# untitled.net
KiCad netlist of a schematic drawn in EAGLE
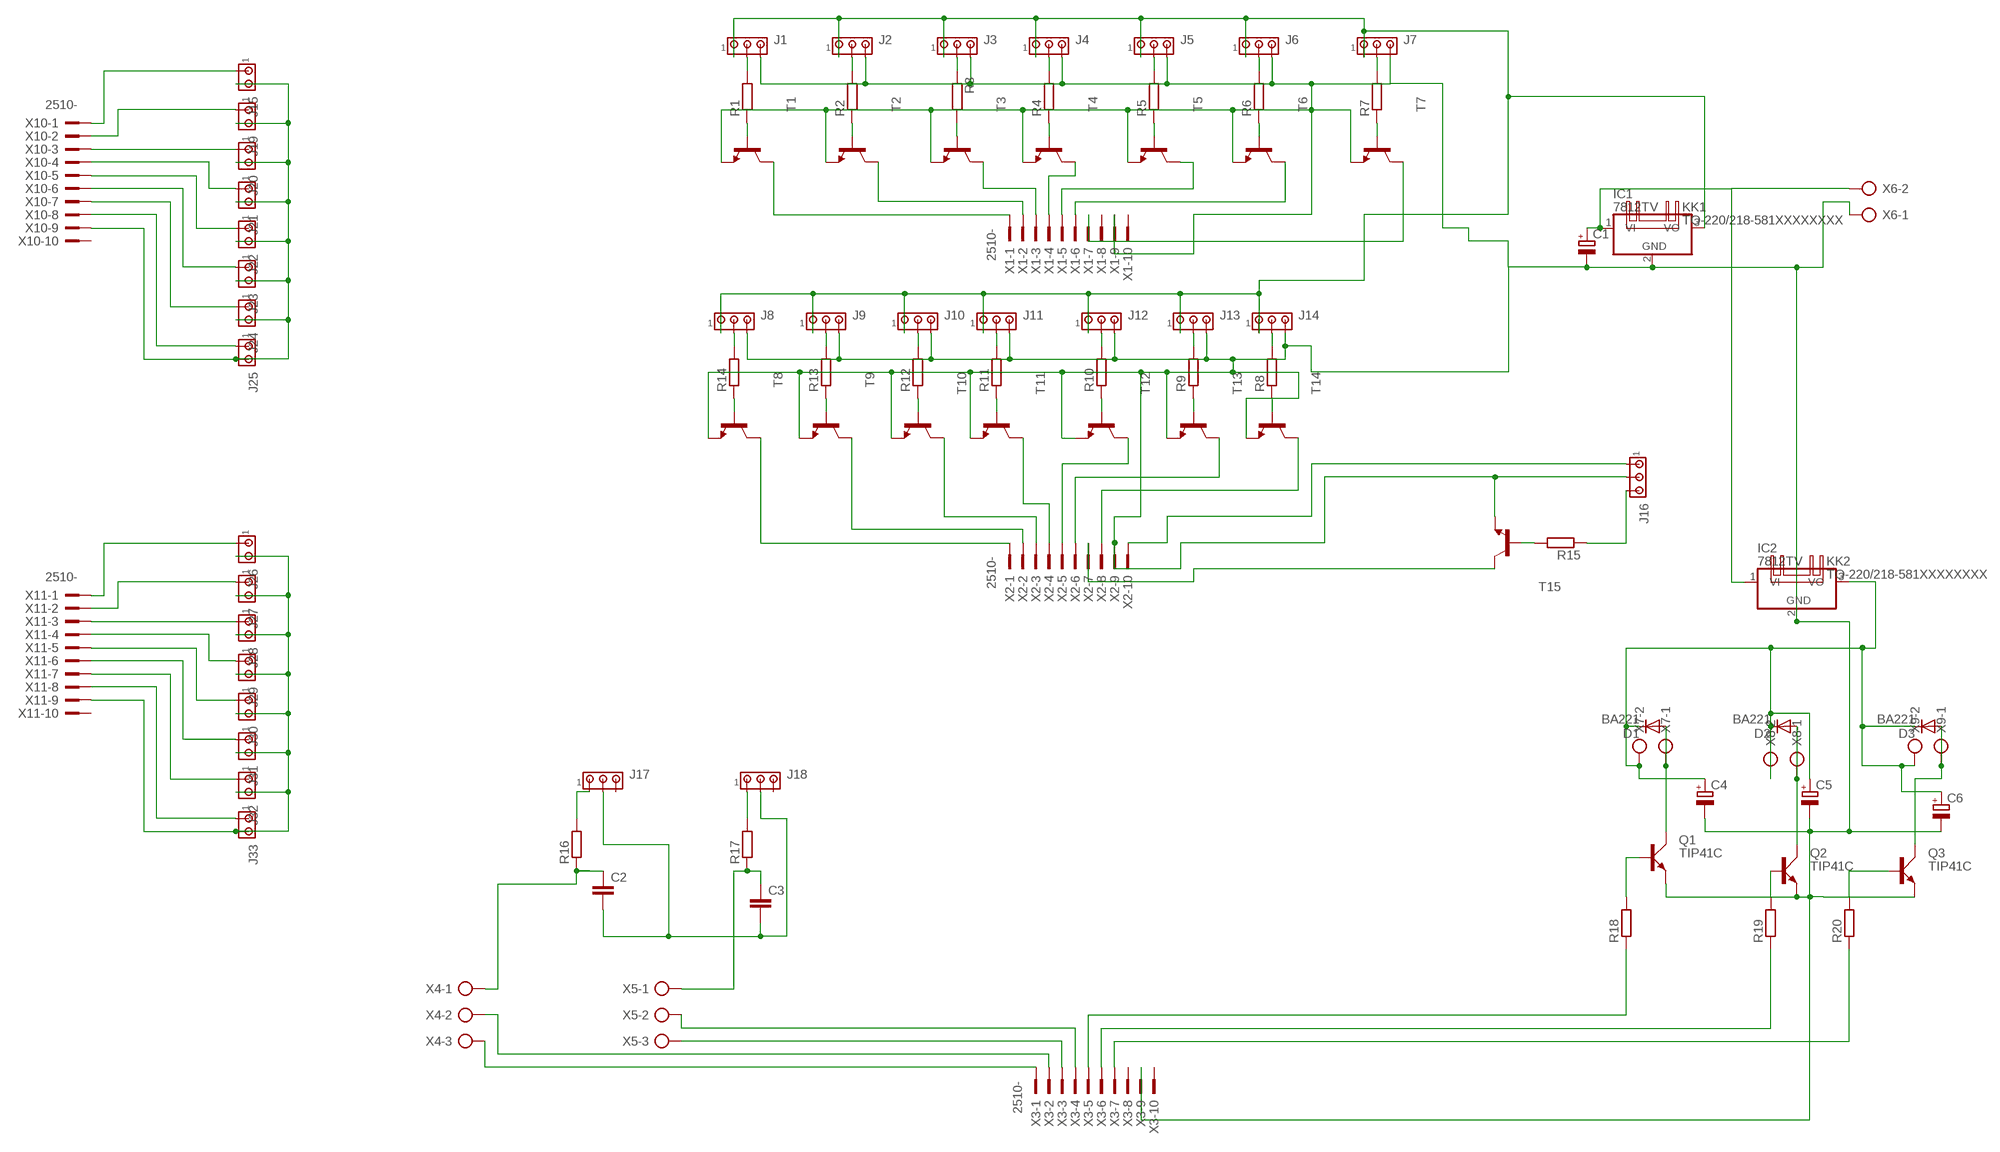
[diagram p0: schematic, sheet 1]
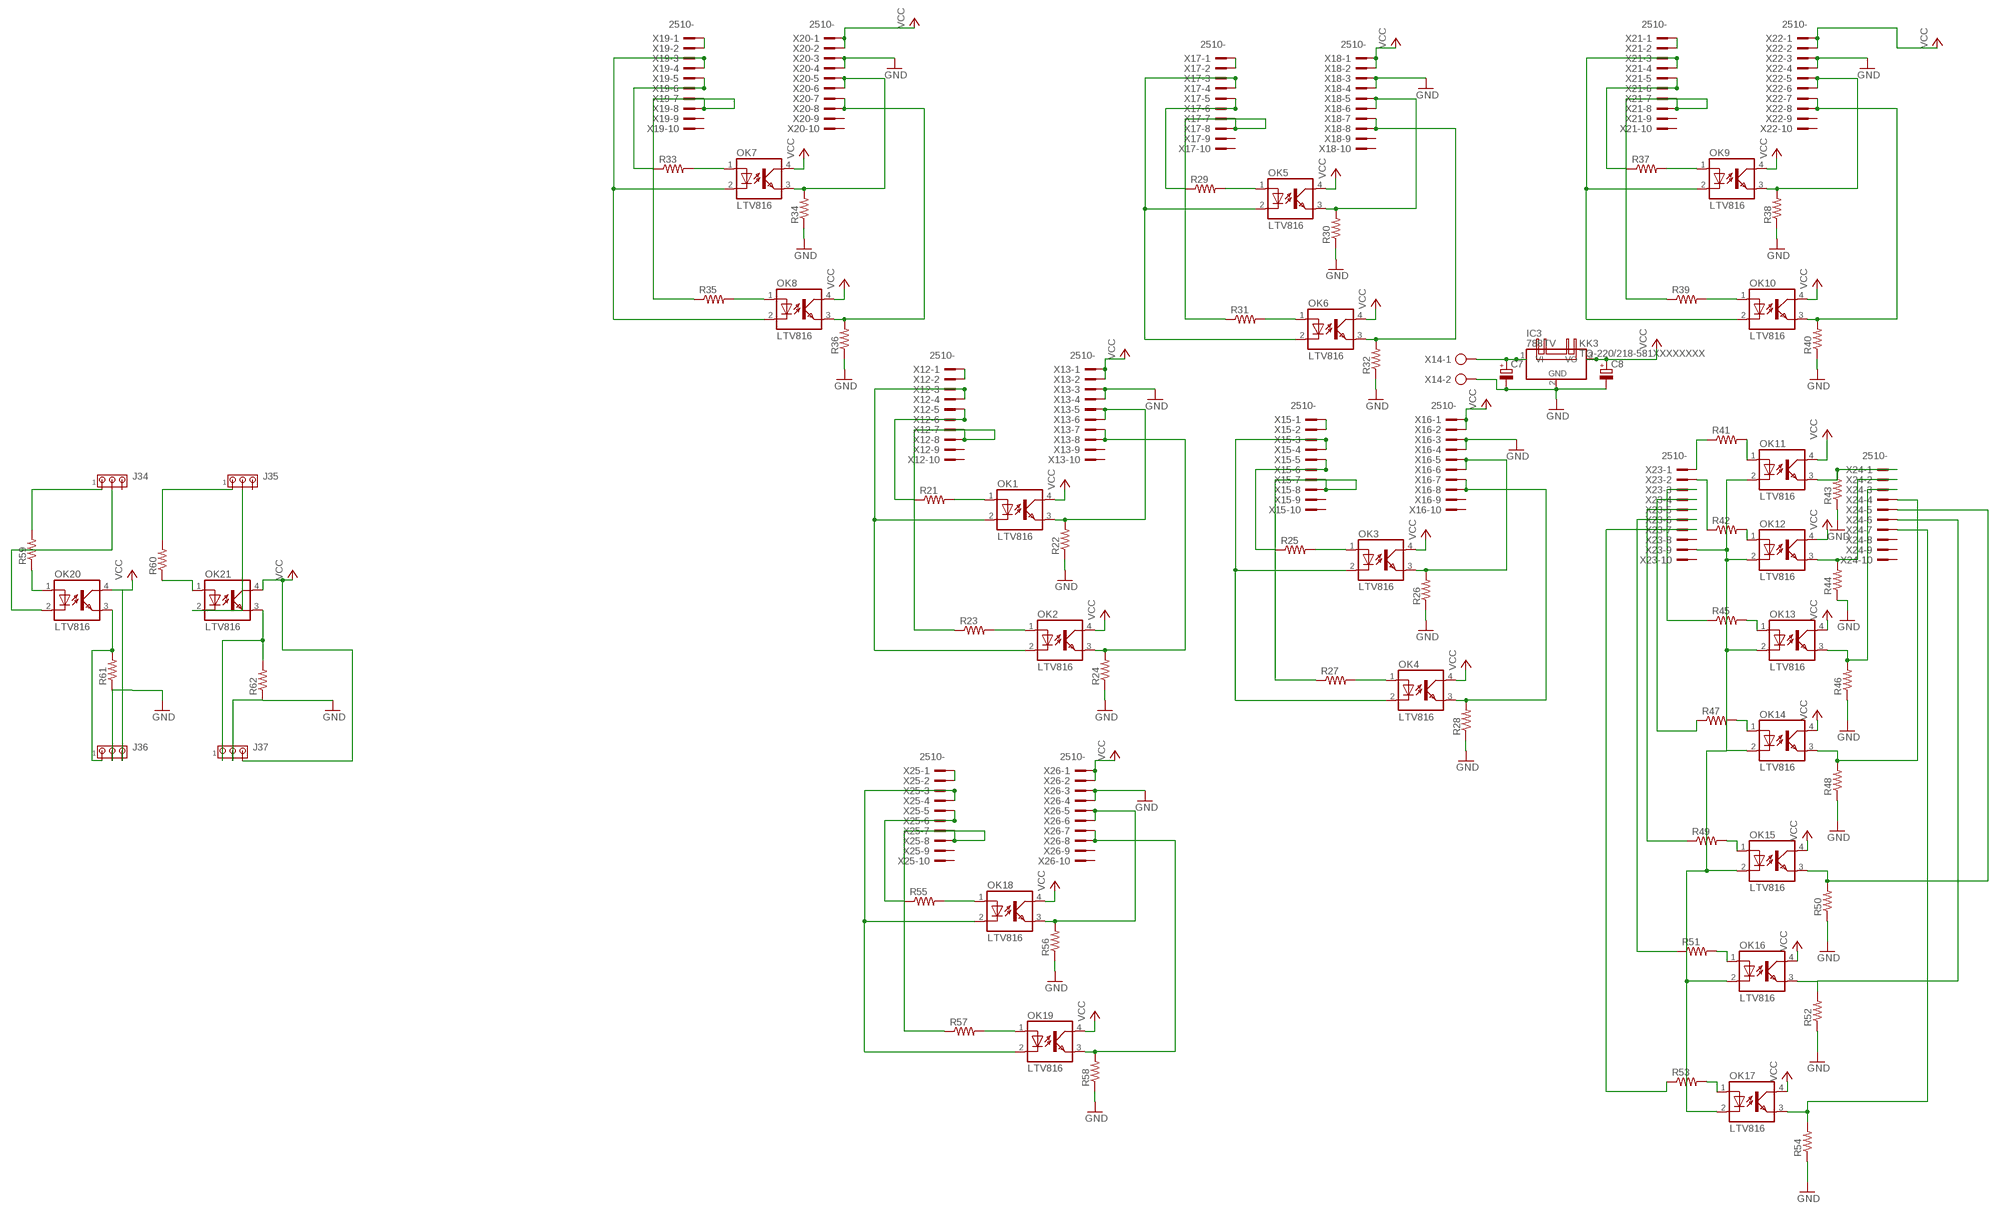
[diagram p1: schematic, sheet 2]

(export (version "E")
  (design (tool "Eeschema 10.0.6"))
  (components
    (comp (ref "C1")
      (value "CPOL-EUE5-10.5")
      (footprint "eagle-import:E5-10,5")
      (libsource (lib "eagle-import") (part "CPOL-EUE5-10.5"))
    )
    (comp (ref "C2")
      (value "C-EU375-192X418")
      (footprint "eagle-import:C375-192X418")
      (libsource (lib "eagle-import") (part "C-EU375-192X418"))
    )
    (comp (ref "C3")
      (value "C-EU375-192X418")
      (footprint "eagle-import:C375-192X418")
      (libsource (lib "eagle-import") (part "C-EU375-192X418"))
    )
    (comp (ref "C4")
      (value "CPOL-EUE5-13")
      (footprint "eagle-import:E5-13")
      (libsource (lib "eagle-import") (part "resistor_CPOL-EUE5-13"))
    )
    (comp (ref "C5")
      (value "CPOL-EUE5-13")
      (footprint "eagle-import:E5-13")
      (libsource (lib "eagle-import") (part "resistor_CPOL-EUE5-13"))
    )
    (comp (ref "C6")
      (value "CPOL-EUE5-13")
      (footprint "eagle-import:E5-13")
      (libsource (lib "eagle-import") (part "resistor_CPOL-EUE5-13"))
    )
    (comp (ref "D1")
      (value "BA221")
      (footprint "eagle-import:DO35-10")
      (libsource (lib "eagle-import") (part "BA221"))
    )
    (comp (ref "D2")
      (value "BA221")
      (footprint "eagle-import:DO35-10")
      (libsource (lib "eagle-import") (part "BA221"))
    )
    (comp (ref "D3")
      (value "BA221")
      (footprint "eagle-import:DO35-10")
      (libsource (lib "eagle-import") (part "BA221"))
    )
    (comp (ref "IC1")
      (value "7812TV")
      (footprint "eagle-import:TO220V")
      (libsource (lib "eagle-import") (part "78TV12"))
    )
    (comp (ref "IC2")
      (value "7812TV")
      (footprint "eagle-import:TO220V")
      (libsource (lib "eagle-import") (part "78TV12"))
    )
    (comp (ref "J1")
      (value "MTA03-100")
      (footprint "eagle-import:10X03MTA")
      (libsource (lib "eagle-import") (part "MTA03-100"))
    )
    (comp (ref "J2")
      (value "MTA03-100")
      (footprint "eagle-import:10X03MTA")
      (libsource (lib "eagle-import") (part "MTA03-100"))
    )
    (comp (ref "J3")
      (value "MTA03-100")
      (footprint "eagle-import:10X03MTA")
      (libsource (lib "eagle-import") (part "MTA03-100"))
    )
    (comp (ref "J4")
      (value "MTA03-100")
      (footprint "eagle-import:10X03MTA")
      (libsource (lib "eagle-import") (part "MTA03-100"))
    )
    (comp (ref "J5")
      (value "MTA03-100")
      (footprint "eagle-import:10X03MTA")
      (libsource (lib "eagle-import") (part "MTA03-100"))
    )
    (comp (ref "J6")
      (value "MTA03-100")
      (footprint "eagle-import:10X03MTA")
      (libsource (lib "eagle-import") (part "MTA03-100"))
    )
    (comp (ref "J7")
      (value "MTA03-100")
      (footprint "eagle-import:10X03MTA")
      (libsource (lib "eagle-import") (part "MTA03-100"))
    )
    (comp (ref "J8")
      (value "MTA03-100")
      (footprint "eagle-import:10X03MTA")
      (libsource (lib "eagle-import") (part "MTA03-100"))
    )
    (comp (ref "J9")
      (value "MTA03-100")
      (footprint "eagle-import:10X03MTA")
      (libsource (lib "eagle-import") (part "MTA03-100"))
    )
    (comp (ref "J10")
      (value "MTA03-100")
      (footprint "eagle-import:10X03MTA")
      (libsource (lib "eagle-import") (part "MTA03-100"))
    )
    (comp (ref "J11")
      (value "MTA03-100")
      (footprint "eagle-import:10X03MTA")
      (libsource (lib "eagle-import") (part "MTA03-100"))
    )
    (comp (ref "J12")
      (value "MTA03-100")
      (footprint "eagle-import:10X03MTA")
      (libsource (lib "eagle-import") (part "MTA03-100"))
    )
    (comp (ref "J13")
      (value "MTA03-100")
      (footprint "eagle-import:10X03MTA")
      (libsource (lib "eagle-import") (part "MTA03-100"))
    )
    (comp (ref "J14")
      (value "MTA03-100")
      (footprint "eagle-import:10X03MTA")
      (libsource (lib "eagle-import") (part "MTA03-100"))
    )
    (comp (ref "J15")
      (value "MTA02-100")
      (footprint "eagle-import:10X02MTA")
      (libsource (lib "eagle-import") (part "MTA02-100"))
    )
    (comp (ref "J16")
      (value "MTA03-100")
      (footprint "eagle-import:10X03MTA")
      (libsource (lib "eagle-import") (part "MTA03-100"))
    )
    (comp (ref "J17")
      (value "MTA03-100")
      (footprint "eagle-import:10X03MTA")
      (libsource (lib "eagle-import") (part "MTA03-100"))
    )
    (comp (ref "J18")
      (value "MTA03-100")
      (footprint "eagle-import:10X03MTA")
      (libsource (lib "eagle-import") (part "MTA03-100"))
    )
    (comp (ref "J19")
      (value "MTA02-100")
      (footprint "eagle-import:10X02MTA")
      (libsource (lib "eagle-import") (part "MTA02-100"))
    )
    (comp (ref "J20")
      (value "MTA02-100")
      (footprint "eagle-import:10X02MTA")
      (libsource (lib "eagle-import") (part "MTA02-100"))
    )
    (comp (ref "J21")
      (value "MTA02-100")
      (footprint "eagle-import:10X02MTA")
      (libsource (lib "eagle-import") (part "MTA02-100"))
    )
    (comp (ref "J22")
      (value "MTA02-100")
      (footprint "eagle-import:10X02MTA")
      (libsource (lib "eagle-import") (part "MTA02-100"))
    )
    (comp (ref "J23")
      (value "MTA02-100")
      (footprint "eagle-import:10X02MTA")
      (libsource (lib "eagle-import") (part "MTA02-100"))
    )
    (comp (ref "J24")
      (value "MTA02-100")
      (footprint "eagle-import:10X02MTA")
      (libsource (lib "eagle-import") (part "MTA02-100"))
    )
    (comp (ref "J25")
      (value "MTA02-100")
      (footprint "eagle-import:10X02MTA")
      (libsource (lib "eagle-import") (part "MTA02-100"))
    )
    (comp (ref "J26")
      (value "MTA02-100")
      (footprint "eagle-import:10X02MTA")
      (libsource (lib "eagle-import") (part "MTA02-100"))
    )
    (comp (ref "J27")
      (value "MTA02-100")
      (footprint "eagle-import:10X02MTA")
      (libsource (lib "eagle-import") (part "MTA02-100"))
    )
    (comp (ref "J28")
      (value "MTA02-100")
      (footprint "eagle-import:10X02MTA")
      (libsource (lib "eagle-import") (part "MTA02-100"))
    )
    (comp (ref "J29")
      (value "MTA02-100")
      (footprint "eagle-import:10X02MTA")
      (libsource (lib "eagle-import") (part "MTA02-100"))
    )
    (comp (ref "J30")
      (value "MTA02-100")
      (footprint "eagle-import:10X02MTA")
      (libsource (lib "eagle-import") (part "MTA02-100"))
    )
    (comp (ref "J31")
      (value "MTA02-100")
      (footprint "eagle-import:10X02MTA")
      (libsource (lib "eagle-import") (part "MTA02-100"))
    )
    (comp (ref "J32")
      (value "MTA02-100")
      (footprint "eagle-import:10X02MTA")
      (libsource (lib "eagle-import") (part "MTA02-100"))
    )
    (comp (ref "J33")
      (value "MTA02-100")
      (footprint "eagle-import:10X02MTA")
      (libsource (lib "eagle-import") (part "MTA02-100"))
    )
    (comp (ref "KK1")
      (value "TO-220/218-581XXXXXXXX")
      (footprint "eagle-import:581XXXXXXXX")
      (libsource (lib "eagle-import") (part "TO-220/218-581XXXXXXXX"))
    )
    (comp (ref "KK2")
      (value "TO-220/218-581XXXXXXXX")
      (footprint "eagle-import:581XXXXXXXX")
      (libsource (lib "eagle-import") (part "TO-220/218-581XXXXXXXX"))
    )
    (comp (ref "Q1")
      (value "TIP41C")
      (footprint "eagle-import:TO220AV")
      (libsource (lib "eagle-import") (part "TIP41C"))
    )
    (comp (ref "Q2")
      (value "TIP41C")
      (footprint "eagle-import:TO220AV")
      (libsource (lib "eagle-import") (part "TIP41C"))
    )
    (comp (ref "Q3")
      (value "TIP41C")
      (footprint "eagle-import:TO220AV")
      (libsource (lib "eagle-import") (part "TIP41C"))
    )
    (comp (ref "R1")
      (value "R-EU_0207/10")
      (footprint "eagle-import:0207_10")
      (libsource (lib "eagle-import") (part "R-EU_0207/10"))
    )
    (comp (ref "R2")
      (value "R-EU_0207/10")
      (footprint "eagle-import:0207_10")
      (libsource (lib "eagle-import") (part "R-EU_0207/10"))
    )
    (comp (ref "R3")
      (value "R-EU_0207/10")
      (footprint "eagle-import:0207_10")
      (libsource (lib "eagle-import") (part "R-EU_0207/10"))
    )
    (comp (ref "R4")
      (value "R-EU_0207/10")
      (footprint "eagle-import:0207_10")
      (libsource (lib "eagle-import") (part "R-EU_0207/10"))
    )
    (comp (ref "R5")
      (value "R-EU_0207/10")
      (footprint "eagle-import:0207_10")
      (libsource (lib "eagle-import") (part "R-EU_0207/10"))
    )
    (comp (ref "R6")
      (value "R-EU_0207/10")
      (footprint "eagle-import:0207_10")
      (libsource (lib "eagle-import") (part "R-EU_0207/10"))
    )
    (comp (ref "R7")
      (value "R-EU_0207/10")
      (footprint "eagle-import:0207_10")
      (libsource (lib "eagle-import") (part "R-EU_0207/10"))
    )
    (comp (ref "R8")
      (value "R-EU_0207/10")
      (footprint "eagle-import:0207_10")
      (libsource (lib "eagle-import") (part "R-EU_0207/10"))
    )
    (comp (ref "R9")
      (value "R-EU_0207/10")
      (footprint "eagle-import:0207_10")
      (libsource (lib "eagle-import") (part "R-EU_0207/10"))
    )
    (comp (ref "R10")
      (value "R-EU_0207/10")
      (footprint "eagle-import:0207_10")
      (libsource (lib "eagle-import") (part "R-EU_0207/10"))
    )
    (comp (ref "R11")
      (value "R-EU_0207/10")
      (footprint "eagle-import:0207_10")
      (libsource (lib "eagle-import") (part "R-EU_0207/10"))
    )
    (comp (ref "R12")
      (value "R-EU_0207/10")
      (footprint "eagle-import:0207_10")
      (libsource (lib "eagle-import") (part "R-EU_0207/10"))
    )
    (comp (ref "R13")
      (value "R-EU_0207/10")
      (footprint "eagle-import:0207_10")
      (libsource (lib "eagle-import") (part "R-EU_0207/10"))
    )
    (comp (ref "R14")
      (value "R-EU_0207/10")
      (footprint "eagle-import:0207_10")
      (libsource (lib "eagle-import") (part "R-EU_0207/10"))
    )
    (comp (ref "R15")
      (value "R-EU_0207/10")
      (footprint "eagle-import:0207_10")
      (libsource (lib "eagle-import") (part "R-EU_0207/10"))
    )
    (comp (ref "R16")
      (value "R-EU_0207/10")
      (footprint "eagle-import:0207_10")
      (libsource (lib "eagle-import") (part "R-EU_0207/10"))
    )
    (comp (ref "R17")
      (value "R-EU_0207/10")
      (footprint "eagle-import:0207_10")
      (libsource (lib "eagle-import") (part "R-EU_0207/10"))
    )
    (comp (ref "R18")
      (value "R-EU_0207/10")
      (footprint "eagle-import:0207_10")
      (libsource (lib "eagle-import") (part "R-EU_0207/10"))
    )
    (comp (ref "R19")
      (value "R-EU_0207/10")
      (footprint "eagle-import:0207_10")
      (libsource (lib "eagle-import") (part "R-EU_0207/10"))
    )
    (comp (ref "R20")
      (value "R-EU_0207/10")
      (footprint "eagle-import:0207_10")
      (libsource (lib "eagle-import") (part "R-EU_0207/10"))
    )
    (comp (ref "T1")
      (value "2N5401-NPN-TO92-CBE")
      (footprint "eagle-import:TO92-CBE")
      (libsource (lib "eagle-import") (part "-NPN-TO92-CBE2N5401"))
    )
    (comp (ref "T2")
      (value "2N5401-NPN-TO92-CBE")
      (footprint "eagle-import:TO92-CBE")
      (libsource (lib "eagle-import") (part "-NPN-TO92-CBE2N5401"))
    )
    (comp (ref "T3")
      (value "2N5401-NPN-TO92-CBE")
      (footprint "eagle-import:TO92-CBE")
      (libsource (lib "eagle-import") (part "-NPN-TO92-CBE2N5401"))
    )
    (comp (ref "T4")
      (value "2N5401-NPN-TO92-CBE")
      (footprint "eagle-import:TO92-CBE")
      (libsource (lib "eagle-import") (part "-NPN-TO92-CBE2N5401"))
    )
    (comp (ref "T5")
      (value "2N5401-NPN-TO92-CBE")
      (footprint "eagle-import:TO92-CBE")
      (libsource (lib "eagle-import") (part "-NPN-TO92-CBE2N5401"))
    )
    (comp (ref "T6")
      (value "2N5401-NPN-TO92-CBE")
      (footprint "eagle-import:TO92-CBE")
      (libsource (lib "eagle-import") (part "-NPN-TO92-CBE2N5401"))
    )
    (comp (ref "T7")
      (value "2N5401-NPN-TO92-CBE")
      (footprint "eagle-import:TO92-CBE")
      (libsource (lib "eagle-import") (part "-NPN-TO92-CBE2N5401"))
    )
    (comp (ref "T8")
      (value "2N5401-NPN-TO92-CBE")
      (footprint "eagle-import:TO92-CBE")
      (libsource (lib "eagle-import") (part "-NPN-TO92-CBE2N5401"))
    )
    (comp (ref "T9")
      (value "2N5401-NPN-TO92-CBE")
      (footprint "eagle-import:TO92-CBE")
      (libsource (lib "eagle-import") (part "-NPN-TO92-CBE2N5401"))
    )
    (comp (ref "T10")
      (value "2N5401-NPN-TO92-CBE")
      (footprint "eagle-import:TO92-CBE")
      (libsource (lib "eagle-import") (part "-NPN-TO92-CBE2N5401"))
    )
    (comp (ref "T11")
      (value "2N5401-NPN-TO92-CBE")
      (footprint "eagle-import:TO92-CBE")
      (libsource (lib "eagle-import") (part "-NPN-TO92-CBE2N5401"))
    )
    (comp (ref "T12")
      (value "2N5401-NPN-TO92-CBE")
      (footprint "eagle-import:TO92-CBE")
      (libsource (lib "eagle-import") (part "-NPN-TO92-CBE2N5401"))
    )
    (comp (ref "T13")
      (value "2N5401-NPN-TO92-CBE")
      (footprint "eagle-import:TO92-CBE")
      (libsource (lib "eagle-import") (part "-NPN-TO92-CBE2N5401"))
    )
    (comp (ref "T14")
      (value "2N5401-NPN-TO92-CBE")
      (footprint "eagle-import:TO92-CBE")
      (libsource (lib "eagle-import") (part "-NPN-TO92-CBE2N5401"))
    )
    (comp (ref "T15")
      (value "2N5401-NPN-TO92-CBE")
      (footprint "eagle-import:TO92-CBE")
      (libsource (lib "eagle-import") (part "-NPN-TO92-CBE2N5401"))
    )
    (comp (ref "X1")
      (value "2510-")
      (footprint "eagle-import:PAK100_2500-10")
      (fields (field (name "MF") "3M") (field (name "MPN") "2510-6002UB"))
      (libsource (lib "eagle-import") (part "2510-"))
    )
    (comp (ref "X2")
      (value "2510-")
      (footprint "eagle-import:PAK100_2500-10")
      (fields (field (name "MF") "3M") (field (name "MPN") "2510-6002UB"))
      (libsource (lib "eagle-import") (part "2510-"))
    )
    (comp (ref "X3")
      (value "2510-")
      (footprint "eagle-import:PAK100_2500-10")
      (fields (field (name "MF") "3M") (field (name "MPN") "2510-6002UB"))
      (libsource (lib "eagle-import") (part "2510-"))
    )
    (comp (ref "X4")
      (value "AK300/3")
      (footprint "eagle-import:AK300_3")
      (libsource (lib "eagle-import") (part "AK300/3"))
    )
    (comp (ref "X5")
      (value "AK300/3")
      (footprint "eagle-import:AK300_3")
      (libsource (lib "eagle-import") (part "AK300/3"))
    )
    (comp (ref "X6")
      (value "AK300/2")
      (footprint "eagle-import:AK300_2")
      (libsource (lib "eagle-import") (part "AK300/2"))
    )
    (comp (ref "X7")
      (value "AK300/2")
      (footprint "eagle-import:AK300_2")
      (libsource (lib "eagle-import") (part "AK300/2"))
    )
    (comp (ref "X8")
      (value "AK300/2")
      (footprint "eagle-import:AK300_2")
      (libsource (lib "eagle-import") (part "AK300/2"))
    )
    (comp (ref "X9")
      (value "AK300/2")
      (footprint "eagle-import:AK300_2")
      (libsource (lib "eagle-import") (part "AK300/2"))
    )
    (comp (ref "X10")
      (value "2510-")
      (footprint "eagle-import:PAK100_2500-10")
      (fields (field (name "MF") "3M") (field (name "MPN") "2510-6002UB"))
      (libsource (lib "eagle-import") (part "2510-"))
    )
    (comp (ref "X11")
      (value "2510-")
      (footprint "eagle-import:PAK100_2500-10")
      (fields (field (name "MF") "3M") (field (name "MPN") "2510-6002UB"))
      (libsource (lib "eagle-import") (part "2510-"))
    )
    (comp (ref "C7")
      (value "CPOL-EUE5-13")
      (footprint "eagle-import:E5-13")
      (libsource (lib "eagle-import") (part "CPOL-EUE5-13"))
    )
    (comp (ref "C8")
      (value "CPOL-EUE5-10.5")
      (footprint "eagle-import:E5-10,5")
      (libsource (lib "eagle-import") (part "CPOL-EUE5-10.5"))
    )
    (comp (ref "IC3")
      (value "788TV")
      (footprint "eagle-import:TO220V")
      (libsource (lib "eagle-import") (part "78TV8"))
    )
    (comp (ref "J34")
      (value "MTA03-100")
      (footprint "eagle-import:10X03MTA")
      (libsource (lib "eagle-import") (part "MTA03-100"))
    )
    (comp (ref "J35")
      (value "MTA03-100")
      (footprint "eagle-import:10X03MTA")
      (libsource (lib "eagle-import") (part "MTA03-100"))
    )
    (comp (ref "J36")
      (value "MTA03-100")
      (footprint "eagle-import:10X03MTA")
      (libsource (lib "eagle-import") (part "MTA03-100"))
    )
    (comp (ref "J37")
      (value "MTA03-100")
      (footprint "eagle-import:10X03MTA")
      (libsource (lib "eagle-import") (part "MTA03-100"))
    )
    (comp (ref "KK3")
      (value "TO-220/218-581XXXXXXXX")
      (footprint "eagle-import:581XXXXXXXX")
      (libsource (lib "eagle-import") (part "TO-220/218-581XXXXXXXX"))
    )
    (comp (ref "OK1")
      (value "LTV816")
      (footprint "eagle-import:DIL04")
      (libsource (lib "eagle-import") (part "LTV816"))
    )
    (comp (ref "OK2")
      (value "LTV816")
      (footprint "eagle-import:DIL04")
      (libsource (lib "eagle-import") (part "LTV816"))
    )
    (comp (ref "OK3")
      (value "LTV816")
      (footprint "eagle-import:DIL04")
      (libsource (lib "eagle-import") (part "LTV816"))
    )
    (comp (ref "OK4")
      (value "LTV816")
      (footprint "eagle-import:DIL04")
      (libsource (lib "eagle-import") (part "LTV816"))
    )
    (comp (ref "OK5")
      (value "LTV816")
      (footprint "eagle-import:DIL04")
      (libsource (lib "eagle-import") (part "LTV816"))
    )
    (comp (ref "OK6")
      (value "LTV816")
      (footprint "eagle-import:DIL04")
      (libsource (lib "eagle-import") (part "LTV816"))
    )
    (comp (ref "OK7")
      (value "LTV816")
      (footprint "eagle-import:DIL04")
      (libsource (lib "eagle-import") (part "LTV816"))
    )
    (comp (ref "OK8")
      (value "LTV816")
      (footprint "eagle-import:DIL04")
      (libsource (lib "eagle-import") (part "LTV816"))
    )
    (comp (ref "OK9")
      (value "LTV816")
      (footprint "eagle-import:DIL04")
      (libsource (lib "eagle-import") (part "LTV816"))
    )
    (comp (ref "OK10")
      (value "LTV816")
      (footprint "eagle-import:DIL04")
      (libsource (lib "eagle-import") (part "LTV816"))
    )
    (comp (ref "OK11")
      (value "LTV816")
      (footprint "eagle-import:DIL04")
      (fields (field (name "OC_FARNELL") "unknown") (field (name "OC_NEWARK") "unknown"))
      (libsource (lib "eagle-import") (part "LTV816"))
    )
    (comp (ref "OK12")
      (value "LTV816")
      (footprint "eagle-import:DIL04")
      (fields (field (name "OC_FARNELL") "unknown") (field (name "OC_NEWARK") "unknown"))
      (libsource (lib "eagle-import") (part "LTV816"))
    )
    (comp (ref "OK13")
      (value "LTV816")
      (footprint "eagle-import:DIL04")
      (fields (field (name "OC_FARNELL") "unknown") (field (name "OC_NEWARK") "unknown"))
      (libsource (lib "eagle-import") (part "LTV816"))
    )
    (comp (ref "OK14")
      (value "LTV816")
      (footprint "eagle-import:DIL04")
      (fields (field (name "OC_FARNELL") "unknown") (field (name "OC_NEWARK") "unknown"))
      (libsource (lib "eagle-import") (part "LTV816"))
    )
    (comp (ref "OK15")
      (value "LTV816")
      (footprint "eagle-import:DIL04")
      (fields (field (name "OC_FARNELL") "unknown") (field (name "OC_NEWARK") "unknown"))
      (libsource (lib "eagle-import") (part "LTV816"))
    )
    (comp (ref "OK16")
      (value "LTV816")
      (footprint "eagle-import:DIL04")
      (fields (field (name "OC_FARNELL") "unknown") (field (name "OC_NEWARK") "unknown"))
      (libsource (lib "eagle-import") (part "LTV816"))
    )
    (comp (ref "OK17")
      (value "LTV816")
      (footprint "eagle-import:DIL04")
      (fields (field (name "OC_FARNELL") "unknown") (field (name "OC_NEWARK") "unknown"))
      (libsource (lib "eagle-import") (part "LTV816"))
    )
    (comp (ref "OK18")
      (value "LTV816")
      (footprint "eagle-import:DIL04")
      (libsource (lib "eagle-import") (part "LTV816"))
    )
    (comp (ref "OK19")
      (value "LTV816")
      (footprint "eagle-import:DIL04")
      (libsource (lib "eagle-import") (part "LTV816"))
    )
    (comp (ref "OK20")
      (value "LTV816")
      (footprint "eagle-import:DIL04")
      (fields (field (name "OC_FARNELL") "unknown") (field (name "OC_NEWARK") "unknown"))
      (libsource (lib "eagle-import") (part "LTV816"))
    )
    (comp (ref "OK21")
      (value "LTV816")
      (footprint "eagle-import:DIL04")
      (fields (field (name "OC_FARNELL") "unknown") (field (name "OC_NEWARK") "unknown"))
      (libsource (lib "eagle-import") (part "LTV816"))
    )
    (comp (ref "R21")
      (value "R-US_0207/10")
      (footprint "eagle-import:0207_10")
      (libsource (lib "eagle-import") (part "R-US_0207/10"))
    )
    (comp (ref "R22")
      (value "R-US_0207/10")
      (footprint "eagle-import:0207_10")
      (libsource (lib "eagle-import") (part "R-US_0207/10"))
    )
    (comp (ref "R23")
      (value "R-US_0207/10")
      (footprint "eagle-import:0207_10")
      (libsource (lib "eagle-import") (part "R-US_0207/10"))
    )
    (comp (ref "R24")
      (value "R-US_0207/10")
      (footprint "eagle-import:0207_10")
      (libsource (lib "eagle-import") (part "R-US_0207/10"))
    )
    (comp (ref "R25")
      (value "R-US_0207/10")
      (footprint "eagle-import:0207_10")
      (libsource (lib "eagle-import") (part "R-US_0207/10"))
    )
    (comp (ref "R26")
      (value "R-US_0207/10")
      (footprint "eagle-import:0207_10")
      (libsource (lib "eagle-import") (part "R-US_0207/10"))
    )
    (comp (ref "R27")
      (value "R-US_0207/10")
      (footprint "eagle-import:0207_10")
      (libsource (lib "eagle-import") (part "R-US_0207/10"))
    )
    (comp (ref "R28")
      (value "R-US_0207/10")
      (footprint "eagle-import:0207_10")
      (libsource (lib "eagle-import") (part "R-US_0207/10"))
    )
    (comp (ref "R29")
      (value "R-US_0207/10")
      (footprint "eagle-import:0207_10")
      (libsource (lib "eagle-import") (part "R-US_0207/10"))
    )
    (comp (ref "R30")
      (value "R-US_0207/10")
      (footprint "eagle-import:0207_10")
      (libsource (lib "eagle-import") (part "R-US_0207/10"))
    )
    (comp (ref "R31")
      (value "R-US_0207/10")
      (footprint "eagle-import:0207_10")
      (libsource (lib "eagle-import") (part "R-US_0207/10"))
    )
    (comp (ref "R32")
      (value "R-US_0207/10")
      (footprint "eagle-import:0207_10")
      (libsource (lib "eagle-import") (part "R-US_0207/10"))
    )
    (comp (ref "R33")
      (value "R-US_0207/10")
      (footprint "eagle-import:0207_10")
      (libsource (lib "eagle-import") (part "R-US_0207/10"))
    )
    (comp (ref "R34")
      (value "R-US_0207/10")
      (footprint "eagle-import:0207_10")
      (libsource (lib "eagle-import") (part "R-US_0207/10"))
    )
    (comp (ref "R35")
      (value "R-US_0207/10")
      (footprint "eagle-import:0207_10")
      (libsource (lib "eagle-import") (part "R-US_0207/10"))
    )
    (comp (ref "R36")
      (value "R-US_0207/10")
      (footprint "eagle-import:0207_10")
      (libsource (lib "eagle-import") (part "R-US_0207/10"))
    )
    (comp (ref "R37")
      (value "R-US_0207/10")
      (footprint "eagle-import:0207_10")
      (libsource (lib "eagle-import") (part "R-US_0207/10"))
    )
    (comp (ref "R38")
      (value "R-US_0207/10")
      (footprint "eagle-import:0207_10")
      (libsource (lib "eagle-import") (part "R-US_0207/10"))
    )
    (comp (ref "R39")
      (value "R-US_0207/10")
      (footprint "eagle-import:0207_10")
      (libsource (lib "eagle-import") (part "R-US_0207/10"))
    )
    (comp (ref "R40")
      (value "R-US_0207/10")
      (footprint "eagle-import:0207_10")
      (libsource (lib "eagle-import") (part "R-US_0207/10"))
    )
    (comp (ref "R41")
      (value "R-US_0207/10")
      (footprint "eagle-import:0207_10")
      (libsource (lib "eagle-import") (part "R-US_0207/10"))
    )
    (comp (ref "R42")
      (value "R-US_0207/10")
      (footprint "eagle-import:0207_10")
      (libsource (lib "eagle-import") (part "R-US_0207/10"))
    )
    (comp (ref "R43")
      (value "R-US_0207/10")
      (footprint "eagle-import:0207_10")
      (libsource (lib "eagle-import") (part "R-US_0207/10"))
    )
    (comp (ref "R44")
      (value "R-US_0207/10")
      (footprint "eagle-import:0207_10")
      (libsource (lib "eagle-import") (part "R-US_0207/10"))
    )
    (comp (ref "R45")
      (value "R-US_0207/10")
      (footprint "eagle-import:0207_10")
      (libsource (lib "eagle-import") (part "R-US_0207/10"))
    )
    (comp (ref "R46")
      (value "R-US_0207/10")
      (footprint "eagle-import:0207_10")
      (libsource (lib "eagle-import") (part "R-US_0207/10"))
    )
    (comp (ref "R47")
      (value "R-US_0207/10")
      (footprint "eagle-import:0207_10")
      (libsource (lib "eagle-import") (part "R-US_0207/10"))
    )
    (comp (ref "R48")
      (value "R-US_0207/10")
      (footprint "eagle-import:0207_10")
      (libsource (lib "eagle-import") (part "R-US_0207/10"))
    )
    (comp (ref "R49")
      (value "R-US_0207/10")
      (footprint "eagle-import:0207_10")
      (libsource (lib "eagle-import") (part "R-US_0207/10"))
    )
    (comp (ref "R50")
      (value "R-US_0207/10")
      (footprint "eagle-import:0207_10")
      (libsource (lib "eagle-import") (part "R-US_0207/10"))
    )
    (comp (ref "R51")
      (value "R-US_0207/10")
      (footprint "eagle-import:0207_10")
      (libsource (lib "eagle-import") (part "R-US_0207/10"))
    )
    (comp (ref "R52")
      (value "R-US_0207/10")
      (footprint "eagle-import:0207_10")
      (libsource (lib "eagle-import") (part "R-US_0207/10"))
    )
    (comp (ref "R53")
      (value "R-US_0207/10")
      (footprint "eagle-import:0207_10")
      (libsource (lib "eagle-import") (part "R-US_0207/10"))
    )
    (comp (ref "R54")
      (value "R-US_0207/10")
      (footprint "eagle-import:0207_10")
      (libsource (lib "eagle-import") (part "R-US_0207/10"))
    )
    (comp (ref "R55")
      (value "R-US_0207/10")
      (footprint "eagle-import:0207_10")
      (libsource (lib "eagle-import") (part "R-US_0207/10"))
    )
    (comp (ref "R56")
      (value "R-US_0207/10")
      (footprint "eagle-import:0207_10")
      (libsource (lib "eagle-import") (part "R-US_0207/10"))
    )
    (comp (ref "R57")
      (value "R-US_0207/10")
      (footprint "eagle-import:0207_10")
      (libsource (lib "eagle-import") (part "R-US_0207/10"))
    )
    (comp (ref "R58")
      (value "R-US_0207/10")
      (footprint "eagle-import:0207_10")
      (libsource (lib "eagle-import") (part "R-US_0207/10"))
    )
    (comp (ref "R59")
      (value "R-US_0207/10")
      (footprint "eagle-import:0207_10")
      (libsource (lib "eagle-import") (part "R-US_0207/10"))
    )
    (comp (ref "R60")
      (value "R-US_0207/10")
      (footprint "eagle-import:0207_10")
      (libsource (lib "eagle-import") (part "R-US_0207/10"))
    )
    (comp (ref "R61")
      (value "R-US_0207/10")
      (footprint "eagle-import:0207_10")
      (libsource (lib "eagle-import") (part "R-US_0207/10"))
    )
    (comp (ref "R62")
      (value "R-US_0207/10")
      (footprint "eagle-import:0207_10")
      (libsource (lib "eagle-import") (part "R-US_0207/10"))
    )
    (comp (ref "X12")
      (value "2510-")
      (footprint "eagle-import:PAK100_2500-10")
      (fields (field (name "MF") "3M") (field (name "MPN") "2510-6002UB"))
      (libsource (lib "eagle-import") (part "2510-"))
    )
    (comp (ref "X13")
      (value "2510-")
      (footprint "eagle-import:PAK100_2500-10")
      (fields (field (name "MF") "3M") (field (name "MPN") "2510-6002UB"))
      (libsource (lib "eagle-import") (part "2510-"))
    )
    (comp (ref "X14")
      (value "AK300/2")
      (footprint "eagle-import:AK300_2")
      (libsource (lib "eagle-import") (part "AK300/2"))
    )
    (comp (ref "X15")
      (value "2510-")
      (footprint "eagle-import:PAK100_2500-10")
      (fields (field (name "MF") "3M") (field (name "MPN") "2510-6002UB"))
      (libsource (lib "eagle-import") (part "2510-"))
    )
    (comp (ref "X16")
      (value "2510-")
      (footprint "eagle-import:PAK100_2500-10")
      (fields (field (name "MF") "3M") (field (name "MPN") "2510-6002UB"))
      (libsource (lib "eagle-import") (part "2510-"))
    )
    (comp (ref "X17")
      (value "2510-")
      (footprint "eagle-import:PAK100_2500-10")
      (fields (field (name "MF") "3M") (field (name "MPN") "2510-6002UB"))
      (libsource (lib "eagle-import") (part "2510-"))
    )
    (comp (ref "X18")
      (value "2510-")
      (footprint "eagle-import:PAK100_2500-10")
      (fields (field (name "MF") "3M") (field (name "MPN") "2510-6002UB"))
      (libsource (lib "eagle-import") (part "2510-"))
    )
    (comp (ref "X19")
      (value "2510-")
      (footprint "eagle-import:PAK100_2500-10")
      (fields (field (name "MF") "3M") (field (name "MPN") "2510-6002UB"))
      (libsource (lib "eagle-import") (part "2510-"))
    )
    (comp (ref "X20")
      (value "2510-")
      (footprint "eagle-import:PAK100_2500-10")
      (fields (field (name "MF") "3M") (field (name "MPN") "2510-6002UB"))
      (libsource (lib "eagle-import") (part "2510-"))
    )
    (comp (ref "X21")
      (value "2510-")
      (footprint "eagle-import:PAK100_2500-10")
      (fields (field (name "MF") "3M") (field (name "MPN") "2510-6002UB"))
      (libsource (lib "eagle-import") (part "2510-"))
    )
    (comp (ref "X22")
      (value "2510-")
      (footprint "eagle-import:PAK100_2500-10")
      (fields (field (name "MF") "3M") (field (name "MPN") "2510-6002UB"))
      (libsource (lib "eagle-import") (part "2510-"))
    )
    (comp (ref "X23")
      (value "2510-")
      (footprint "eagle-import:PAK100_2500-10")
      (fields (field (name "MF") "3M") (field (name "MPN") "2510-6002UB"))
      (libsource (lib "eagle-import") (part "2510-"))
    )
    (comp (ref "X24")
      (value "2510-")
      (footprint "eagle-import:PAK100_2500-10")
      (fields (field (name "MF") "3M") (field (name "MPN") "2510-6002UB"))
      (libsource (lib "eagle-import") (part "2510-"))
    )
    (comp (ref "X25")
      (value "2510-")
      (footprint "eagle-import:PAK100_2500-10")
      (fields (field (name "MF") "3M") (field (name "MPN") "2510-6002UB"))
      (libsource (lib "eagle-import") (part "2510-"))
    )
    (comp (ref "X26")
      (value "2510-")
      (footprint "eagle-import:PAK100_2500-10")
      (fields (field (name "MF") "3M") (field (name "MPN") "2510-6002UB"))
      (libsource (lib "eagle-import") (part "2510-"))
    )
  )
  (nets
    (net (code "1") (name "GND") (class "Default")
      (node (ref "C7") (pin "-") (pinfunction "-_-") (pintype "passive"))
      (node (ref "C8") (pin "-") (pinfunction "-_-") (pintype "passive"))
      (node (ref "IC3") (pin "2") (pinfunction "GND_2") (pintype "passive"))
      (node (ref "J36") (pin "2") (pinfunction "2_2") (pintype "passive"))
      (node (ref "J37") (pin "2") (pinfunction "2_2") (pintype "passive"))
      (node (ref "R22") (pin "1") (pinfunction "1_1") (pintype "passive"))
      (node (ref "R24") (pin "1") (pinfunction "1_1") (pintype "passive"))
      (node (ref "R26") (pin "1") (pinfunction "1_1") (pintype "passive"))
      (node (ref "R28") (pin "1") (pinfunction "1_1") (pintype "passive"))
      (node (ref "R30") (pin "1") (pinfunction "1_1") (pintype "passive"))
      (node (ref "R32") (pin "1") (pinfunction "1_1") (pintype "passive"))
      (node (ref "R34") (pin "1") (pinfunction "1_1") (pintype "passive"))
      (node (ref "R36") (pin "1") (pinfunction "1_1") (pintype "passive"))
      (node (ref "R38") (pin "1") (pinfunction "1_1") (pintype "passive"))
      (node (ref "R40") (pin "1") (pinfunction "1_1") (pintype "passive"))
      (node (ref "R43") (pin "1") (pinfunction "1_1") (pintype "passive"))
      (node (ref "R44") (pin "1") (pinfunction "1_1") (pintype "passive"))
      (node (ref "R46") (pin "1") (pinfunction "1_1") (pintype "passive"))
      (node (ref "R48") (pin "1") (pinfunction "1_1") (pintype "passive"))
      (node (ref "R50") (pin "1") (pinfunction "1_1") (pintype "passive"))
      (node (ref "R52") (pin "1") (pinfunction "1_1") (pintype "passive"))
      (node (ref "R54") (pin "1") (pinfunction "1_1") (pintype "passive"))
      (node (ref "R56") (pin "1") (pinfunction "1_1") (pintype "passive"))
      (node (ref "R58") (pin "1") (pinfunction "1_1") (pintype "passive"))
      (node (ref "R61") (pin "1") (pinfunction "1_1") (pintype "passive"))
      (node (ref "R62") (pin "1") (pinfunction "1_1") (pintype "passive"))
      (node (ref "X13") (pin "3") (pinfunction "KL_3") (pintype "passive"))
      (node (ref "X13") (pin "4") (pinfunction "KL_4") (pintype "passive"))
      (node (ref "X14") (pin "2") (pinfunction "KL_2") (pintype "passive"))
      (node (ref "X16") (pin "3") (pinfunction "KL_3") (pintype "passive"))
      (node (ref "X16") (pin "4") (pinfunction "KL_4") (pintype "passive"))
      (node (ref "X18") (pin "3") (pinfunction "KL_3") (pintype "passive"))
      (node (ref "X18") (pin "4") (pinfunction "KL_4") (pintype "passive"))
      (node (ref "X20") (pin "3") (pinfunction "KL_3") (pintype "passive"))
      (node (ref "X20") (pin "4") (pinfunction "KL_4") (pintype "passive"))
      (node (ref "X22") (pin "3") (pinfunction "KL_3") (pintype "passive"))
      (node (ref "X22") (pin "4") (pinfunction "KL_4") (pintype "passive"))
      (node (ref "X26") (pin "3") (pinfunction "KL_3") (pintype "passive"))
      (node (ref "X26") (pin "4") (pinfunction "KL_4") (pintype "passive"))
    )
    (net (code "2") (name "Net-(C2-Pad2)") (class "Default")
      (node (ref "C2") (pin "2") (pinfunction "2_2") (pintype "passive"))
      (node (ref "C3") (pin "2") (pinfunction "2_2") (pintype "passive"))
      (node (ref "J17") (pin "2") (pinfunction "2_2") (pintype "passive"))
      (node (ref "J18") (pin "2") (pinfunction "2_2") (pintype "passive"))
    )
    (net (code "3") (name "Net-(IC1-GND)") (class "Default")
      (node (ref "C1") (pin "-") (pinfunction "-_-") (pintype "passive"))
      (node (ref "C4") (pin "-") (pinfunction "-_-") (pintype "passive"))
      (node (ref "C5") (pin "-") (pinfunction "-_-") (pintype "passive"))
      (node (ref "C6") (pin "-") (pinfunction "-_-") (pintype "passive"))
      (node (ref "IC1") (pin "2") (pinfunction "GND_2") (pintype "passive"))
      (node (ref "IC2") (pin "2") (pinfunction "GND_2") (pintype "passive"))
      (node (ref "J1") (pin "3") (pinfunction "3_3") (pintype "passive"))
      (node (ref "J10") (pin "3") (pinfunction "3_3") (pintype "passive"))
      (node (ref "J11") (pin "3") (pinfunction "3_3") (pintype "passive"))
      (node (ref "J12") (pin "3") (pinfunction "3_3") (pintype "passive"))
      (node (ref "J13") (pin "3") (pinfunction "3_3") (pintype "passive"))
      (node (ref "J14") (pin "3") (pinfunction "3_3") (pintype "passive"))
      (node (ref "J16") (pin "2") (pinfunction "2_2") (pintype "passive"))
      (node (ref "J2") (pin "3") (pinfunction "3_3") (pintype "passive"))
      (node (ref "J3") (pin "3") (pinfunction "3_3") (pintype "passive"))
      (node (ref "J4") (pin "3") (pinfunction "3_3") (pintype "passive"))
      (node (ref "J5") (pin "3") (pinfunction "3_3") (pintype "passive"))
      (node (ref "J6") (pin "3") (pinfunction "3_3") (pintype "passive"))
      (node (ref "J7") (pin "3") (pinfunction "3_3") (pintype "passive"))
      (node (ref "J8") (pin "3") (pinfunction "3_3") (pintype "passive"))
      (node (ref "J9") (pin "3") (pinfunction "3_3") (pintype "passive"))
      (node (ref "Q1") (pin "E") (pinfunction "E_E") (pintype "passive"))
      (node (ref "Q2") (pin "E") (pinfunction "E_E") (pintype "passive"))
      (node (ref "Q3") (pin "E") (pinfunction "E_E") (pintype "passive"))
      (node (ref "T1") (pin "E") (pinfunction "E_E") (pintype "passive"))
      (node (ref "T10") (pin "E") (pinfunction "E_E") (pintype "passive"))
      (node (ref "T11") (pin "E") (pinfunction "E_E") (pintype "passive"))
      (node (ref "T12") (pin "E") (pinfunction "E_E") (pintype "passive"))
      (node (ref "T13") (pin "E") (pinfunction "E_E") (pintype "passive"))
      (node (ref "T14") (pin "E") (pinfunction "E_E") (pintype "passive"))
      (node (ref "T15") (pin "E") (pinfunction "E_E") (pintype "passive"))
      (node (ref "T2") (pin "E") (pinfunction "E_E") (pintype "passive"))
      (node (ref "T3") (pin "E") (pinfunction "E_E") (pintype "passive"))
      (node (ref "T4") (pin "E") (pinfunction "E_E") (pintype "passive"))
      (node (ref "T5") (pin "E") (pinfunction "E_E") (pintype "passive"))
      (node (ref "T6") (pin "E") (pinfunction "E_E") (pintype "passive"))
      (node (ref "T7") (pin "E") (pinfunction "E_E") (pintype "passive"))
      (node (ref "T8") (pin "E") (pinfunction "E_E") (pintype "passive"))
      (node (ref "T9") (pin "E") (pinfunction "E_E") (pintype "passive"))
      (node (ref "X1") (pin "9") (pinfunction "KL_9") (pintype "passive"))
      (node (ref "X2") (pin "9") (pinfunction "KL_9") (pintype "passive"))
      (node (ref "X3") (pin "9") (pinfunction "KL_9") (pintype "passive"))
      (node (ref "X6") (pin "1") (pinfunction "KL_1") (pintype "passive"))
    )
    (net (code "4") (name "Net-(IC1-VI)") (class "Default")
      (node (ref "C1") (pin "+") (pinfunction "+_+") (pintype "passive"))
      (node (ref "IC1") (pin "1") (pinfunction "VI_1") (pintype "input"))
      (node (ref "IC2") (pin "1") (pinfunction "VI_1") (pintype "input"))
      (node (ref "X6") (pin "2") (pinfunction "KL_2") (pintype "passive"))
    )
    (net (code "5") (name "Net-(IC1-VO)") (class "Default")
      (node (ref "IC1") (pin "3") (pinfunction "VO_3") (pintype "passive"))
      (node (ref "J1") (pin "1") (pinfunction "1_1") (pintype "passive"))
      (node (ref "J10") (pin "1") (pinfunction "1_1") (pintype "passive"))
      (node (ref "J11") (pin "1") (pinfunction "1_1") (pintype "passive"))
      (node (ref "J12") (pin "1") (pinfunction "1_1") (pintype "passive"))
      (node (ref "J13") (pin "1") (pinfunction "1_1") (pintype "passive"))
      (node (ref "J14") (pin "1") (pinfunction "1_1") (pintype "passive"))
      (node (ref "J2") (pin "1") (pinfunction "1_1") (pintype "passive"))
      (node (ref "J3") (pin "1") (pinfunction "1_1") (pintype "passive"))
      (node (ref "J4") (pin "1") (pinfunction "1_1") (pintype "passive"))
      (node (ref "J5") (pin "1") (pinfunction "1_1") (pintype "passive"))
      (node (ref "J6") (pin "1") (pinfunction "1_1") (pintype "passive"))
      (node (ref "J7") (pin "1") (pinfunction "1_1") (pintype "passive"))
      (node (ref "J8") (pin "1") (pinfunction "1_1") (pintype "passive"))
      (node (ref "J9") (pin "1") (pinfunction "1_1") (pintype "passive"))
    )
    (net (code "6") (name "Net-(IC2-VO)") (class "Default")
      (node (ref "C4") (pin "+") (pinfunction "+_+") (pintype "passive"))
      (node (ref "C5") (pin "+") (pinfunction "+_+") (pintype "passive"))
      (node (ref "C6") (pin "+") (pinfunction "+_+") (pintype "passive"))
      (node (ref "D1") (pin "C") (pinfunction "C_C") (pintype "passive"))
      (node (ref "D2") (pin "C") (pinfunction "C_C") (pintype "passive"))
      (node (ref "D3") (pin "C") (pinfunction "C_C") (pintype "passive"))
      (node (ref "IC2") (pin "3") (pinfunction "VO_3") (pintype "passive"))
      (node (ref "X7") (pin "2") (pinfunction "KL_2") (pintype "passive"))
      (node (ref "X8") (pin "2") (pinfunction "KL_2") (pintype "passive"))
      (node (ref "X9") (pin "2") (pinfunction "KL_2") (pintype "passive"))
    )
    (net (code "7") (name "Net-(IC3-VI)") (class "Default")
      (node (ref "C7") (pin "+") (pinfunction "+_+") (pintype "passive"))
      (node (ref "IC3") (pin "1") (pinfunction "VI_1") (pintype "input"))
      (node (ref "X14") (pin "1") (pinfunction "KL_1") (pintype "passive"))
    )
    (net (code "8") (name "Net-(J1-Pad2)") (class "Default")
      (node (ref "J1") (pin "2") (pinfunction "2_2") (pintype "passive"))
      (node (ref "R1") (pin "2") (pinfunction "2_2") (pintype "passive"))
    )
    (net (code "9") (name "Net-(J2-Pad2)") (class "Default")
      (node (ref "J2") (pin "2") (pinfunction "2_2") (pintype "passive"))
      (node (ref "R2") (pin "2") (pinfunction "2_2") (pintype "passive"))
    )
    (net (code "10") (name "Net-(J3-Pad2)") (class "Default")
      (node (ref "J3") (pin "2") (pinfunction "2_2") (pintype "passive"))
      (node (ref "R3") (pin "1") (pinfunction "1_1") (pintype "passive"))
    )
    (net (code "11") (name "Net-(J4-Pad2)") (class "Default")
      (node (ref "J4") (pin "2") (pinfunction "2_2") (pintype "passive"))
      (node (ref "R4") (pin "2") (pinfunction "2_2") (pintype "passive"))
    )
    (net (code "12") (name "Net-(J5-Pad2)") (class "Default")
      (node (ref "J5") (pin "2") (pinfunction "2_2") (pintype "passive"))
      (node (ref "R5") (pin "2") (pinfunction "2_2") (pintype "passive"))
    )
    (net (code "13") (name "Net-(J6-Pad2)") (class "Default")
      (node (ref "J6") (pin "2") (pinfunction "2_2") (pintype "passive"))
      (node (ref "R6") (pin "2") (pinfunction "2_2") (pintype "passive"))
    )
    (net (code "14") (name "Net-(J7-Pad2)") (class "Default")
      (node (ref "J7") (pin "2") (pinfunction "2_2") (pintype "passive"))
      (node (ref "R7") (pin "2") (pinfunction "2_2") (pintype "passive"))
    )
    (net (code "15") (name "Net-(J8-Pad2)") (class "Default")
      (node (ref "J8") (pin "2") (pinfunction "2_2") (pintype "passive"))
      (node (ref "R14") (pin "2") (pinfunction "2_2") (pintype "passive"))
    )
    (net (code "16") (name "Net-(J9-Pad2)") (class "Default")
      (node (ref "J9") (pin "2") (pinfunction "2_2") (pintype "passive"))
      (node (ref "R13") (pin "2") (pinfunction "2_2") (pintype "passive"))
    )
    (net (code "17") (name "Net-(J10-Pad2)") (class "Default")
      (node (ref "J10") (pin "2") (pinfunction "2_2") (pintype "passive"))
      (node (ref "R12") (pin "2") (pinfunction "2_2") (pintype "passive"))
    )
    (net (code "18") (name "Net-(J11-Pad2)") (class "Default")
      (node (ref "J11") (pin "2") (pinfunction "2_2") (pintype "passive"))
      (node (ref "R11") (pin "2") (pinfunction "2_2") (pintype "passive"))
    )
    (net (code "19") (name "Net-(J12-Pad2)") (class "Default")
      (node (ref "J12") (pin "2") (pinfunction "2_2") (pintype "passive"))
      (node (ref "R10") (pin "2") (pinfunction "2_2") (pintype "passive"))
    )
    (net (code "20") (name "Net-(J13-Pad2)") (class "Default")
      (node (ref "J13") (pin "2") (pinfunction "2_2") (pintype "passive"))
      (node (ref "R9") (pin "2") (pinfunction "2_2") (pintype "passive"))
    )
    (net (code "21") (name "Net-(J14-Pad2)") (class "Default")
      (node (ref "J14") (pin "2") (pinfunction "2_2") (pintype "passive"))
      (node (ref "R8") (pin "2") (pinfunction "2_2") (pintype "passive"))
    )
    (net (code "22") (name "Net-(J16-Pad3)") (class "Default")
      (node (ref "J16") (pin "3") (pinfunction "3_3") (pintype "passive"))
      (node (ref "R15") (pin "1") (pinfunction "1_1") (pintype "passive"))
    )
    (net (code "23") (name "Net-(J17-Pad1)") (class "Default")
      (node (ref "J17") (pin "1") (pinfunction "1_1") (pintype "passive"))
      (node (ref "R16") (pin "2") (pinfunction "2_2") (pintype "passive"))
    )
    (net (code "24") (name "Net-(J18-Pad1)") (class "Default")
      (node (ref "J18") (pin "1") (pinfunction "1_1") (pintype "passive"))
      (node (ref "R17") (pin "2") (pinfunction "2_2") (pintype "passive"))
    )
    (net (code "25") (name "Net-(J34-Pad1)") (class "Default")
      (node (ref "J34") (pin "1") (pinfunction "1_1") (pintype "passive"))
      (node (ref "R59") (pin "2") (pinfunction "2_2") (pintype "passive"))
    )
    (net (code "26") (name "Net-(J35-Pad1)") (class "Default")
      (node (ref "J35") (pin "1") (pinfunction "1_1") (pintype "passive"))
      (node (ref "R60") (pin "2") (pinfunction "2_2") (pintype "passive"))
    )
    (net (code "27") (name "Net-(OK1-A)") (class "Default")
      (node (ref "OK1") (pin "1") (pinfunction "A_1") (pintype "passive"))
      (node (ref "R21") (pin "2") (pinfunction "2_2") (pintype "passive"))
    )
    (net (code "28") (name "Net-(OK1-C)") (class "Default")
      (node (ref "OK1") (pin "2") (pinfunction "C_2") (pintype "passive"))
      (node (ref "OK2") (pin "2") (pinfunction "C_2") (pintype "passive"))
      (node (ref "X12") (pin "3") (pinfunction "KL_3") (pintype "passive"))
      (node (ref "X12") (pin "4") (pinfunction "KL_4") (pintype "passive"))
    )
    (net (code "29") (name "Net-(OK1-EMIT)") (class "Default")
      (node (ref "OK1") (pin "3") (pinfunction "EMIT_3") (pintype "passive"))
      (node (ref "R22") (pin "2") (pinfunction "2_2") (pintype "passive"))
      (node (ref "X13") (pin "5") (pinfunction "KL_5") (pintype "passive"))
      (node (ref "X13") (pin "6") (pinfunction "KL_6") (pintype "passive"))
    )
    (net (code "30") (name "Net-(OK2-A)") (class "Default")
      (node (ref "OK2") (pin "1") (pinfunction "A_1") (pintype "passive"))
      (node (ref "R23") (pin "2") (pinfunction "2_2") (pintype "passive"))
    )
    (net (code "31") (name "Net-(OK2-EMIT)") (class "Default")
      (node (ref "OK2") (pin "3") (pinfunction "EMIT_3") (pintype "passive"))
      (node (ref "R24") (pin "2") (pinfunction "2_2") (pintype "passive"))
      (node (ref "X13") (pin "7") (pinfunction "KL_7") (pintype "passive"))
      (node (ref "X13") (pin "8") (pinfunction "KL_8") (pintype "passive"))
    )
    (net (code "32") (name "Net-(OK3-A)") (class "Default")
      (node (ref "OK3") (pin "1") (pinfunction "A_1") (pintype "passive"))
      (node (ref "R25") (pin "2") (pinfunction "2_2") (pintype "passive"))
    )
    (net (code "33") (name "Net-(OK3-C)") (class "Default")
      (node (ref "OK3") (pin "2") (pinfunction "C_2") (pintype "passive"))
      (node (ref "OK4") (pin "2") (pinfunction "C_2") (pintype "passive"))
      (node (ref "X15") (pin "3") (pinfunction "KL_3") (pintype "passive"))
      (node (ref "X15") (pin "4") (pinfunction "KL_4") (pintype "passive"))
    )
    (net (code "34") (name "Net-(OK3-EMIT)") (class "Default")
      (node (ref "OK3") (pin "3") (pinfunction "EMIT_3") (pintype "passive"))
      (node (ref "R26") (pin "2") (pinfunction "2_2") (pintype "passive"))
      (node (ref "X16") (pin "5") (pinfunction "KL_5") (pintype "passive"))
      (node (ref "X16") (pin "6") (pinfunction "KL_6") (pintype "passive"))
    )
    (net (code "35") (name "Net-(OK4-A)") (class "Default")
      (node (ref "OK4") (pin "1") (pinfunction "A_1") (pintype "passive"))
      (node (ref "R27") (pin "2") (pinfunction "2_2") (pintype "passive"))
    )
    (net (code "36") (name "Net-(OK4-EMIT)") (class "Default")
      (node (ref "OK4") (pin "3") (pinfunction "EMIT_3") (pintype "passive"))
      (node (ref "R28") (pin "2") (pinfunction "2_2") (pintype "passive"))
      (node (ref "X16") (pin "7") (pinfunction "KL_7") (pintype "passive"))
      (node (ref "X16") (pin "8") (pinfunction "KL_8") (pintype "passive"))
    )
    (net (code "37") (name "Net-(OK5-A)") (class "Default")
      (node (ref "OK5") (pin "1") (pinfunction "A_1") (pintype "passive"))
      (node (ref "R29") (pin "2") (pinfunction "2_2") (pintype "passive"))
    )
    (net (code "38") (name "Net-(OK5-C)") (class "Default")
      (node (ref "OK5") (pin "2") (pinfunction "C_2") (pintype "passive"))
      (node (ref "OK6") (pin "2") (pinfunction "C_2") (pintype "passive"))
      (node (ref "X17") (pin "3") (pinfunction "KL_3") (pintype "passive"))
      (node (ref "X17") (pin "4") (pinfunction "KL_4") (pintype "passive"))
    )
    (net (code "39") (name "Net-(OK5-EMIT)") (class "Default")
      (node (ref "OK5") (pin "3") (pinfunction "EMIT_3") (pintype "passive"))
      (node (ref "R30") (pin "2") (pinfunction "2_2") (pintype "passive"))
      (node (ref "X18") (pin "5") (pinfunction "KL_5") (pintype "passive"))
      (node (ref "X18") (pin "6") (pinfunction "KL_6") (pintype "passive"))
    )
    (net (code "40") (name "Net-(OK6-A)") (class "Default")
      (node (ref "OK6") (pin "1") (pinfunction "A_1") (pintype "passive"))
      (node (ref "R31") (pin "2") (pinfunction "2_2") (pintype "passive"))
    )
    (net (code "41") (name "Net-(OK6-EMIT)") (class "Default")
      (node (ref "OK6") (pin "3") (pinfunction "EMIT_3") (pintype "passive"))
      (node (ref "R32") (pin "2") (pinfunction "2_2") (pintype "passive"))
      (node (ref "X18") (pin "7") (pinfunction "KL_7") (pintype "passive"))
      (node (ref "X18") (pin "8") (pinfunction "KL_8") (pintype "passive"))
    )
    (net (code "42") (name "Net-(OK7-A)") (class "Default")
      (node (ref "OK7") (pin "1") (pinfunction "A_1") (pintype "passive"))
      (node (ref "R33") (pin "2") (pinfunction "2_2") (pintype "passive"))
    )
    (net (code "43") (name "Net-(OK7-C)") (class "Default")
      (node (ref "OK7") (pin "2") (pinfunction "C_2") (pintype "passive"))
      (node (ref "OK8") (pin "2") (pinfunction "C_2") (pintype "passive"))
      (node (ref "X19") (pin "3") (pinfunction "KL_3") (pintype "passive"))
      (node (ref "X19") (pin "4") (pinfunction "KL_4") (pintype "passive"))
    )
    (net (code "44") (name "Net-(OK7-EMIT)") (class "Default")
      (node (ref "OK7") (pin "3") (pinfunction "EMIT_3") (pintype "passive"))
      (node (ref "R34") (pin "2") (pinfunction "2_2") (pintype "passive"))
      (node (ref "X20") (pin "5") (pinfunction "KL_5") (pintype "passive"))
      (node (ref "X20") (pin "6") (pinfunction "KL_6") (pintype "passive"))
    )
    (net (code "45") (name "Net-(OK8-A)") (class "Default")
      (node (ref "OK8") (pin "1") (pinfunction "A_1") (pintype "passive"))
      (node (ref "R35") (pin "2") (pinfunction "2_2") (pintype "passive"))
    )
    (net (code "46") (name "Net-(OK8-EMIT)") (class "Default")
      (node (ref "OK8") (pin "3") (pinfunction "EMIT_3") (pintype "passive"))
      (node (ref "R36") (pin "2") (pinfunction "2_2") (pintype "passive"))
      (node (ref "X20") (pin "7") (pinfunction "KL_7") (pintype "passive"))
      (node (ref "X20") (pin "8") (pinfunction "KL_8") (pintype "passive"))
    )
    (net (code "47") (name "Net-(OK9-A)") (class "Default")
      (node (ref "OK9") (pin "1") (pinfunction "A_1") (pintype "passive"))
      (node (ref "R37") (pin "2") (pinfunction "2_2") (pintype "passive"))
    )
    (net (code "48") (name "Net-(OK9-EMIT)") (class "Default")
      (node (ref "OK9") (pin "3") (pinfunction "EMIT_3") (pintype "passive"))
      (node (ref "R38") (pin "2") (pinfunction "2_2") (pintype "passive"))
      (node (ref "X22") (pin "5") (pinfunction "KL_5") (pintype "passive"))
      (node (ref "X22") (pin "6") (pinfunction "KL_6") (pintype "passive"))
    )
    (net (code "49") (name "Net-(OK10-A)") (class "Default")
      (node (ref "OK10") (pin "1") (pinfunction "A_1") (pintype "passive"))
      (node (ref "R39") (pin "2") (pinfunction "2_2") (pintype "passive"))
    )
    (net (code "50") (name "Net-(OK10-C)") (class "Default")
      (node (ref "OK10") (pin "2") (pinfunction "C_2") (pintype "passive"))
      (node (ref "OK9") (pin "2") (pinfunction "C_2") (pintype "passive"))
      (node (ref "X21") (pin "3") (pinfunction "KL_3") (pintype "passive"))
      (node (ref "X21") (pin "4") (pinfunction "KL_4") (pintype "passive"))
    )
    (net (code "51") (name "Net-(OK10-EMIT)") (class "Default")
      (node (ref "OK10") (pin "3") (pinfunction "EMIT_3") (pintype "passive"))
      (node (ref "R40") (pin "2") (pinfunction "2_2") (pintype "passive"))
      (node (ref "X22") (pin "7") (pinfunction "KL_7") (pintype "passive"))
      (node (ref "X22") (pin "8") (pinfunction "KL_8") (pintype "passive"))
    )
    (net (code "52") (name "Net-(OK11-A)") (class "Default")
      (node (ref "OK11") (pin "1") (pinfunction "A_1") (pintype "passive"))
      (node (ref "R41") (pin "2") (pinfunction "2_2") (pintype "passive"))
    )
    (net (code "53") (name "Net-(OK11-C)") (class "Default")
      (node (ref "OK11") (pin "2") (pinfunction "C_2") (pintype "passive"))
      (node (ref "OK12") (pin "2") (pinfunction "C_2") (pintype "passive"))
      (node (ref "OK13") (pin "2") (pinfunction "C_2") (pintype "passive"))
      (node (ref "OK14") (pin "2") (pinfunction "C_2") (pintype "passive"))
      (node (ref "OK15") (pin "2") (pinfunction "C_2") (pintype "passive"))
      (node (ref "OK16") (pin "2") (pinfunction "C_2") (pintype "passive"))
      (node (ref "OK17") (pin "2") (pinfunction "C_2") (pintype "passive"))
      (node (ref "X23") (pin "9") (pinfunction "KL_9") (pintype "passive"))
    )
    (net (code "54") (name "Net-(OK11-EMIT)") (class "Default")
      (node (ref "OK11") (pin "3") (pinfunction "EMIT_3") (pintype "passive"))
      (node (ref "R43") (pin "2") (pinfunction "2_2") (pintype "passive"))
      (node (ref "X24") (pin "1") (pinfunction "KL_1") (pintype "passive"))
    )
    (net (code "55") (name "Net-(OK12-A)") (class "Default")
      (node (ref "OK12") (pin "1") (pinfunction "A_1") (pintype "passive"))
      (node (ref "R42") (pin "2") (pinfunction "2_2") (pintype "passive"))
    )
    (net (code "56") (name "Net-(OK12-EMIT)") (class "Default")
      (node (ref "OK12") (pin "3") (pinfunction "EMIT_3") (pintype "passive"))
      (node (ref "R44") (pin "2") (pinfunction "2_2") (pintype "passive"))
      (node (ref "X24") (pin "2") (pinfunction "KL_2") (pintype "passive"))
    )
    (net (code "57") (name "Net-(OK13-A)") (class "Default")
      (node (ref "OK13") (pin "1") (pinfunction "A_1") (pintype "passive"))
      (node (ref "R45") (pin "2") (pinfunction "2_2") (pintype "passive"))
    )
    (net (code "58") (name "Net-(OK13-EMIT)") (class "Default")
      (node (ref "OK13") (pin "3") (pinfunction "EMIT_3") (pintype "passive"))
      (node (ref "R46") (pin "2") (pinfunction "2_2") (pintype "passive"))
      (node (ref "X24") (pin "3") (pinfunction "KL_3") (pintype "passive"))
    )
    (net (code "59") (name "Net-(OK14-A)") (class "Default")
      (node (ref "OK14") (pin "1") (pinfunction "A_1") (pintype "passive"))
      (node (ref "R47") (pin "2") (pinfunction "2_2") (pintype "passive"))
    )
    (net (code "60") (name "Net-(OK14-EMIT)") (class "Default")
      (node (ref "OK14") (pin "3") (pinfunction "EMIT_3") (pintype "passive"))
      (node (ref "R48") (pin "2") (pinfunction "2_2") (pintype "passive"))
      (node (ref "X24") (pin "4") (pinfunction "KL_4") (pintype "passive"))
    )
    (net (code "61") (name "Net-(OK15-A)") (class "Default")
      (node (ref "OK15") (pin "1") (pinfunction "A_1") (pintype "passive"))
      (node (ref "R49") (pin "2") (pinfunction "2_2") (pintype "passive"))
    )
    (net (code "62") (name "Net-(OK15-EMIT)") (class "Default")
      (node (ref "OK15") (pin "3") (pinfunction "EMIT_3") (pintype "passive"))
      (node (ref "R50") (pin "2") (pinfunction "2_2") (pintype "passive"))
      (node (ref "X24") (pin "5") (pinfunction "KL_5") (pintype "passive"))
    )
    (net (code "63") (name "Net-(OK16-A)") (class "Default")
      (node (ref "OK16") (pin "1") (pinfunction "A_1") (pintype "passive"))
      (node (ref "R51") (pin "2") (pinfunction "2_2") (pintype "passive"))
    )
    (net (code "64") (name "Net-(OK16-EMIT)") (class "Default")
      (node (ref "OK16") (pin "3") (pinfunction "EMIT_3") (pintype "passive"))
      (node (ref "R52") (pin "2") (pinfunction "2_2") (pintype "passive"))
      (node (ref "X24") (pin "6") (pinfunction "KL_6") (pintype "passive"))
    )
    (net (code "65") (name "Net-(OK17-A)") (class "Default")
      (node (ref "OK17") (pin "1") (pinfunction "A_1") (pintype "passive"))
      (node (ref "R53") (pin "2") (pinfunction "2_2") (pintype "passive"))
    )
    (net (code "66") (name "Net-(OK17-EMIT)") (class "Default")
      (node (ref "OK17") (pin "3") (pinfunction "EMIT_3") (pintype "passive"))
      (node (ref "R54") (pin "2") (pinfunction "2_2") (pintype "passive"))
      (node (ref "X24") (pin "7") (pinfunction "KL_7") (pintype "passive"))
    )
    (net (code "67") (name "Net-(OK18-A)") (class "Default")
      (node (ref "OK18") (pin "1") (pinfunction "A_1") (pintype "passive"))
      (node (ref "R55") (pin "2") (pinfunction "2_2") (pintype "passive"))
    )
    (net (code "68") (name "Net-(OK18-C)") (class "Default")
      (node (ref "OK18") (pin "2") (pinfunction "C_2") (pintype "passive"))
      (node (ref "OK19") (pin "2") (pinfunction "C_2") (pintype "passive"))
      (node (ref "X25") (pin "3") (pinfunction "KL_3") (pintype "passive"))
      (node (ref "X25") (pin "4") (pinfunction "KL_4") (pintype "passive"))
    )
    (net (code "69") (name "Net-(OK18-EMIT)") (class "Default")
      (node (ref "OK18") (pin "3") (pinfunction "EMIT_3") (pintype "passive"))
      (node (ref "R56") (pin "2") (pinfunction "2_2") (pintype "passive"))
      (node (ref "X26") (pin "5") (pinfunction "KL_5") (pintype "passive"))
      (node (ref "X26") (pin "6") (pinfunction "KL_6") (pintype "passive"))
    )
    (net (code "70") (name "Net-(OK19-A)") (class "Default")
      (node (ref "OK19") (pin "1") (pinfunction "A_1") (pintype "passive"))
      (node (ref "R57") (pin "2") (pinfunction "2_2") (pintype "passive"))
    )
    (net (code "71") (name "Net-(OK19-EMIT)") (class "Default")
      (node (ref "OK19") (pin "3") (pinfunction "EMIT_3") (pintype "passive"))
      (node (ref "R58") (pin "2") (pinfunction "2_2") (pintype "passive"))
      (node (ref "X26") (pin "7") (pinfunction "KL_7") (pintype "passive"))
      (node (ref "X26") (pin "8") (pinfunction "KL_8") (pintype "passive"))
    )
    (net (code "72") (name "Net-(OK20-A)") (class "Default")
      (node (ref "OK20") (pin "1") (pinfunction "A_1") (pintype "passive"))
      (node (ref "R59") (pin "1") (pinfunction "1_1") (pintype "passive"))
    )
    (net (code "73") (name "Net-(OK20-C)") (class "Default")
      (node (ref "J34") (pin "2") (pinfunction "2_2") (pintype "passive"))
      (node (ref "OK20") (pin "2") (pinfunction "C_2") (pintype "passive"))
    )
    (net (code "74") (name "Net-(OK20-EMIT)") (class "Default")
      (node (ref "J36") (pin "1") (pinfunction "1_1") (pintype "passive"))
      (node (ref "OK20") (pin "3") (pinfunction "EMIT_3") (pintype "passive"))
      (node (ref "R61") (pin "2") (pinfunction "2_2") (pintype "passive"))
    )
    (net (code "75") (name "Net-(OK21-A)") (class "Default")
      (node (ref "OK21") (pin "1") (pinfunction "A_1") (pintype "passive"))
      (node (ref "R60") (pin "1") (pinfunction "1_1") (pintype "passive"))
    )
    (net (code "76") (name "Net-(OK21-C)") (class "Default")
      (node (ref "J35") (pin "2") (pinfunction "2_2") (pintype "passive"))
      (node (ref "OK21") (pin "2") (pinfunction "C_2") (pintype "passive"))
    )
    (net (code "77") (name "Net-(OK21-EMIT)") (class "Default")
      (node (ref "J37") (pin "1") (pinfunction "1_1") (pintype "passive"))
      (node (ref "OK21") (pin "3") (pinfunction "EMIT_3") (pintype "passive"))
      (node (ref "R62") (pin "2") (pinfunction "2_2") (pintype "passive"))
    )
    (net (code "78") (name "Net-(Q1-PadB)") (class "Default")
      (node (ref "Q1") (pin "B") (pinfunction "B_B") (pintype "passive"))
      (node (ref "R18") (pin "2") (pinfunction "2_2") (pintype "passive"))
    )
    (net (code "79") (name "Net-(Q2-PadB)") (class "Default")
      (node (ref "Q2") (pin "B") (pinfunction "B_B") (pintype "passive"))
      (node (ref "R19") (pin "2") (pinfunction "2_2") (pintype "passive"))
    )
    (net (code "80") (name "Net-(Q3-PadB)") (class "Default")
      (node (ref "Q3") (pin "B") (pinfunction "B_B") (pintype "passive"))
      (node (ref "R20") (pin "2") (pinfunction "2_2") (pintype "passive"))
    )
    (net (code "81") (name "Net-(R1-Pad1)") (class "Default")
      (node (ref "R1") (pin "1") (pinfunction "1_1") (pintype "passive"))
      (node (ref "T1") (pin "B") (pinfunction "B_B") (pintype "passive"))
    )
    (net (code "82") (name "Net-(R2-Pad1)") (class "Default")
      (node (ref "R2") (pin "1") (pinfunction "1_1") (pintype "passive"))
      (node (ref "T2") (pin "B") (pinfunction "B_B") (pintype "passive"))
    )
    (net (code "83") (name "Net-(R3-Pad2)") (class "Default")
      (node (ref "R3") (pin "2") (pinfunction "2_2") (pintype "passive"))
      (node (ref "T3") (pin "B") (pinfunction "B_B") (pintype "passive"))
    )
    (net (code "84") (name "Net-(R4-Pad1)") (class "Default")
      (node (ref "R4") (pin "1") (pinfunction "1_1") (pintype "passive"))
      (node (ref "T4") (pin "B") (pinfunction "B_B") (pintype "passive"))
    )
    (net (code "85") (name "Net-(R5-Pad1)") (class "Default")
      (node (ref "R5") (pin "1") (pinfunction "1_1") (pintype "passive"))
      (node (ref "T5") (pin "B") (pinfunction "B_B") (pintype "passive"))
    )
    (net (code "86") (name "Net-(R6-Pad1)") (class "Default")
      (node (ref "R6") (pin "1") (pinfunction "1_1") (pintype "passive"))
      (node (ref "T6") (pin "B") (pinfunction "B_B") (pintype "passive"))
    )
    (net (code "87") (name "Net-(R7-Pad1)") (class "Default")
      (node (ref "R7") (pin "1") (pinfunction "1_1") (pintype "passive"))
      (node (ref "T7") (pin "B") (pinfunction "B_B") (pintype "passive"))
    )
    (net (code "88") (name "Net-(R8-Pad1)") (class "Default")
      (node (ref "R8") (pin "1") (pinfunction "1_1") (pintype "passive"))
      (node (ref "T14") (pin "B") (pinfunction "B_B") (pintype "passive"))
    )
    (net (code "89") (name "Net-(R9-Pad1)") (class "Default")
      (node (ref "R9") (pin "1") (pinfunction "1_1") (pintype "passive"))
      (node (ref "T13") (pin "B") (pinfunction "B_B") (pintype "passive"))
    )
    (net (code "90") (name "Net-(R10-Pad1)") (class "Default")
      (node (ref "R10") (pin "1") (pinfunction "1_1") (pintype "passive"))
      (node (ref "T12") (pin "B") (pinfunction "B_B") (pintype "passive"))
    )
    (net (code "91") (name "Net-(R11-Pad1)") (class "Default")
      (node (ref "R11") (pin "1") (pinfunction "1_1") (pintype "passive"))
      (node (ref "T11") (pin "B") (pinfunction "B_B") (pintype "passive"))
    )
    (net (code "92") (name "Net-(R12-Pad1)") (class "Default")
      (node (ref "R12") (pin "1") (pinfunction "1_1") (pintype "passive"))
      (node (ref "T10") (pin "B") (pinfunction "B_B") (pintype "passive"))
    )
    (net (code "93") (name "Net-(R13-Pad1)") (class "Default")
      (node (ref "R13") (pin "1") (pinfunction "1_1") (pintype "passive"))
      (node (ref "T9") (pin "B") (pinfunction "B_B") (pintype "passive"))
    )
    (net (code "94") (name "Net-(R14-Pad1)") (class "Default")
      (node (ref "R14") (pin "1") (pinfunction "1_1") (pintype "passive"))
      (node (ref "T8") (pin "B") (pinfunction "B_B") (pintype "passive"))
    )
    (net (code "95") (name "Net-(R15-Pad2)") (class "Default")
      (node (ref "R15") (pin "2") (pinfunction "2_2") (pintype "passive"))
      (node (ref "T15") (pin "B") (pinfunction "B_B") (pintype "passive"))
    )
    (net (code "96") (name "Net-(X1A-KL)") (class "Default")
      (node (ref "T1") (pin "C") (pinfunction "C_C") (pintype "passive"))
      (node (ref "X1") (pin "1") (pinfunction "KL_1") (pintype "passive"))
    )
    (net (code "97") (name "Net-(X1C-KL)") (class "Default")
      (node (ref "T2") (pin "C") (pinfunction "C_C") (pintype "passive"))
      (node (ref "X1") (pin "2") (pinfunction "KL_2") (pintype "passive"))
    )
    (net (code "98") (name "Net-(X1D-KL)") (class "Default")
      (node (ref "T3") (pin "C") (pinfunction "C_C") (pintype "passive"))
      (node (ref "X1") (pin "3") (pinfunction "KL_3") (pintype "passive"))
    )
    (net (code "99") (name "Net-(X1E-KL)") (class "Default")
      (node (ref "T4") (pin "C") (pinfunction "C_C") (pintype "passive"))
      (node (ref "X1") (pin "4") (pinfunction "KL_4") (pintype "passive"))
    )
    (net (code "100") (name "Net-(X1F-KL)") (class "Default")
      (node (ref "T5") (pin "C") (pinfunction "C_C") (pintype "passive"))
      (node (ref "X1") (pin "5") (pinfunction "KL_5") (pintype "passive"))
    )
    (net (code "101") (name "Net-(X1G-KL)") (class "Default")
      (node (ref "T6") (pin "C") (pinfunction "C_C") (pintype "passive"))
      (node (ref "X1") (pin "6") (pinfunction "KL_6") (pintype "passive"))
    )
    (net (code "102") (name "Net-(X1H-KL)") (class "Default")
      (node (ref "T7") (pin "C") (pinfunction "C_C") (pintype "passive"))
      (node (ref "X1") (pin "7") (pinfunction "KL_7") (pintype "passive"))
    )
    (net (code "103") (name "Net-(X2A-KL)") (class "Default")
      (node (ref "T8") (pin "C") (pinfunction "C_C") (pintype "passive"))
      (node (ref "X2") (pin "1") (pinfunction "KL_1") (pintype "passive"))
    )
    (net (code "104") (name "Net-(X2B-KL)") (class "Default")
      (node (ref "J16") (pin "1") (pinfunction "1_1") (pintype "passive"))
      (node (ref "X2") (pin "10") (pinfunction "KL_10") (pintype "passive"))
    )
    (net (code "105") (name "Net-(X2C-KL)") (class "Default")
      (node (ref "T9") (pin "C") (pinfunction "C_C") (pintype "passive"))
      (node (ref "X2") (pin "2") (pinfunction "KL_2") (pintype "passive"))
    )
    (net (code "106") (name "Net-(X2D-KL)") (class "Default")
      (node (ref "T10") (pin "C") (pinfunction "C_C") (pintype "passive"))
      (node (ref "X2") (pin "3") (pinfunction "KL_3") (pintype "passive"))
    )
    (net (code "107") (name "Net-(X2E-KL)") (class "Default")
      (node (ref "T11") (pin "C") (pinfunction "C_C") (pintype "passive"))
      (node (ref "X2") (pin "4") (pinfunction "KL_4") (pintype "passive"))
    )
    (net (code "108") (name "Net-(X2F-KL)") (class "Default")
      (node (ref "T12") (pin "C") (pinfunction "C_C") (pintype "passive"))
      (node (ref "X2") (pin "5") (pinfunction "KL_5") (pintype "passive"))
    )
    (net (code "109") (name "Net-(X2G-KL)") (class "Default")
      (node (ref "T13") (pin "C") (pinfunction "C_C") (pintype "passive"))
      (node (ref "X2") (pin "6") (pinfunction "KL_6") (pintype "passive"))
    )
    (net (code "110") (name "Net-(X2H-KL)") (class "Default")
      (node (ref "T15") (pin "C") (pinfunction "C_C") (pintype "passive"))
      (node (ref "X2") (pin "7") (pinfunction "KL_7") (pintype "passive"))
    )
    (net (code "111") (name "Net-(X2I-KL)") (class "Default")
      (node (ref "T14") (pin "C") (pinfunction "C_C") (pintype "passive"))
      (node (ref "X2") (pin "8") (pinfunction "KL_8") (pintype "passive"))
    )
    (net (code "112") (name "Net-(X3A-KL)") (class "Default")
      (node (ref "X3") (pin "1") (pinfunction "KL_1") (pintype "passive"))
      (node (ref "X4") (pin "3") (pinfunction "KL_3") (pintype "passive"))
    )
    (net (code "113") (name "Net-(X3C-KL)") (class "Default")
      (node (ref "X3") (pin "2") (pinfunction "KL_2") (pintype "passive"))
      (node (ref "X4") (pin "2") (pinfunction "KL_2") (pintype "passive"))
    )
    (net (code "114") (name "Net-(X3D-KL)") (class "Default")
      (node (ref "X3") (pin "3") (pinfunction "KL_3") (pintype "passive"))
      (node (ref "X5") (pin "3") (pinfunction "KL_3") (pintype "passive"))
    )
    (net (code "115") (name "Net-(X3E-KL)") (class "Default")
      (node (ref "X3") (pin "4") (pinfunction "KL_4") (pintype "passive"))
      (node (ref "X5") (pin "2") (pinfunction "KL_2") (pintype "passive"))
    )
    (net (code "116") (name "Net-(X3F-KL)") (class "Default")
      (node (ref "R18") (pin "1") (pinfunction "1_1") (pintype "passive"))
      (node (ref "X3") (pin "5") (pinfunction "KL_5") (pintype "passive"))
    )
    (net (code "117") (name "Net-(X3G-KL)") (class "Default")
      (node (ref "R19") (pin "1") (pinfunction "1_1") (pintype "passive"))
      (node (ref "X3") (pin "6") (pinfunction "KL_6") (pintype "passive"))
    )
    (net (code "118") (name "Net-(X3H-KL)") (class "Default")
      (node (ref "R20") (pin "1") (pinfunction "1_1") (pintype "passive"))
      (node (ref "X3") (pin "7") (pinfunction "KL_7") (pintype "passive"))
    )
    (net (code "119") (name "Net-(X4A-KL)") (class "Default")
      (node (ref "C2") (pin "1") (pinfunction "1_1") (pintype "passive"))
      (node (ref "R16") (pin "1") (pinfunction "1_1") (pintype "passive"))
      (node (ref "X4") (pin "1") (pinfunction "KL_1") (pintype "passive"))
    )
    (net (code "120") (name "Net-(X5A-KL)") (class "Default")
      (node (ref "C3") (pin "1") (pinfunction "1_1") (pintype "passive"))
      (node (ref "R17") (pin "1") (pinfunction "1_1") (pintype "passive"))
      (node (ref "X5") (pin "1") (pinfunction "KL_1") (pintype "passive"))
    )
    (net (code "121") (name "Net-(X7A-KL)") (class "Default")
      (node (ref "D1") (pin "A") (pinfunction "A_A") (pintype "passive"))
      (node (ref "Q1") (pin "C") (pinfunction "C_C") (pintype "passive"))
      (node (ref "X7") (pin "1") (pinfunction "KL_1") (pintype "passive"))
    )
    (net (code "122") (name "Net-(X8A-KL)") (class "Default")
      (node (ref "D2") (pin "A") (pinfunction "A_A") (pintype "passive"))
      (node (ref "Q2") (pin "C") (pinfunction "C_C") (pintype "passive"))
      (node (ref "X8") (pin "1") (pinfunction "KL_1") (pintype "passive"))
    )
    (net (code "123") (name "Net-(X9A-KL)") (class "Default")
      (node (ref "D3") (pin "A") (pinfunction "A_A") (pintype "passive"))
      (node (ref "Q3") (pin "C") (pinfunction "C_C") (pintype "passive"))
      (node (ref "X9") (pin "1") (pinfunction "KL_1") (pintype "passive"))
    )
    (net (code "124") (name "Net-(X10A-KL)") (class "Default")
      (node (ref "J15") (pin "1") (pinfunction "1_1") (pintype "passive"))
      (node (ref "X10") (pin "1") (pinfunction "KL_1") (pintype "passive"))
    )
    (net (code "125") (name "Net-(X10C-KL)") (class "Default")
      (node (ref "J19") (pin "1") (pinfunction "1_1") (pintype "passive"))
      (node (ref "X10") (pin "2") (pinfunction "KL_2") (pintype "passive"))
    )
    (net (code "126") (name "Net-(X10D-KL)") (class "Default")
      (node (ref "J20") (pin "1") (pinfunction "1_1") (pintype "passive"))
      (node (ref "X10") (pin "3") (pinfunction "KL_3") (pintype "passive"))
    )
    (net (code "127") (name "Net-(X10E-KL)") (class "Default")
      (node (ref "J21") (pin "1") (pinfunction "1_1") (pintype "passive"))
      (node (ref "X10") (pin "4") (pinfunction "KL_4") (pintype "passive"))
    )
    (net (code "128") (name "Net-(X10F-KL)") (class "Default")
      (node (ref "J22") (pin "1") (pinfunction "1_1") (pintype "passive"))
      (node (ref "X10") (pin "5") (pinfunction "KL_5") (pintype "passive"))
    )
    (net (code "129") (name "Net-(X10G-KL)") (class "Default")
      (node (ref "J23") (pin "1") (pinfunction "1_1") (pintype "passive"))
      (node (ref "X10") (pin "6") (pinfunction "KL_6") (pintype "passive"))
    )
    (net (code "130") (name "Net-(X10H-KL)") (class "Default")
      (node (ref "J24") (pin "1") (pinfunction "1_1") (pintype "passive"))
      (node (ref "X10") (pin "7") (pinfunction "KL_7") (pintype "passive"))
    )
    (net (code "131") (name "Net-(X10I-KL)") (class "Default")
      (node (ref "J25") (pin "1") (pinfunction "1_1") (pintype "passive"))
      (node (ref "X10") (pin "8") (pinfunction "KL_8") (pintype "passive"))
    )
    (net (code "132") (name "Net-(X10J-KL)") (class "Default")
      (node (ref "J15") (pin "2") (pinfunction "2_2") (pintype "passive"))
      (node (ref "J19") (pin "2") (pinfunction "2_2") (pintype "passive"))
      (node (ref "J20") (pin "2") (pinfunction "2_2") (pintype "passive"))
      (node (ref "J21") (pin "2") (pinfunction "2_2") (pintype "passive"))
      (node (ref "J22") (pin "2") (pinfunction "2_2") (pintype "passive"))
      (node (ref "J23") (pin "2") (pinfunction "2_2") (pintype "passive"))
      (node (ref "J24") (pin "2") (pinfunction "2_2") (pintype "passive"))
      (node (ref "J25") (pin "2") (pinfunction "2_2") (pintype "passive"))
      (node (ref "X10") (pin "9") (pinfunction "KL_9") (pintype "passive"))
    )
    (net (code "133") (name "Net-(X11A-KL)") (class "Default")
      (node (ref "J26") (pin "1") (pinfunction "1_1") (pintype "passive"))
      (node (ref "X11") (pin "1") (pinfunction "KL_1") (pintype "passive"))
    )
    (net (code "134") (name "Net-(X11C-KL)") (class "Default")
      (node (ref "J27") (pin "1") (pinfunction "1_1") (pintype "passive"))
      (node (ref "X11") (pin "2") (pinfunction "KL_2") (pintype "passive"))
    )
    (net (code "135") (name "Net-(X11D-KL)") (class "Default")
      (node (ref "J28") (pin "1") (pinfunction "1_1") (pintype "passive"))
      (node (ref "X11") (pin "3") (pinfunction "KL_3") (pintype "passive"))
    )
    (net (code "136") (name "Net-(X11E-KL)") (class "Default")
      (node (ref "J29") (pin "1") (pinfunction "1_1") (pintype "passive"))
      (node (ref "X11") (pin "4") (pinfunction "KL_4") (pintype "passive"))
    )
    (net (code "137") (name "Net-(X11F-KL)") (class "Default")
      (node (ref "J30") (pin "1") (pinfunction "1_1") (pintype "passive"))
      (node (ref "X11") (pin "5") (pinfunction "KL_5") (pintype "passive"))
    )
    (net (code "138") (name "Net-(X11G-KL)") (class "Default")
      (node (ref "J31") (pin "1") (pinfunction "1_1") (pintype "passive"))
      (node (ref "X11") (pin "6") (pinfunction "KL_6") (pintype "passive"))
    )
    (net (code "139") (name "Net-(X11H-KL)") (class "Default")
      (node (ref "J32") (pin "1") (pinfunction "1_1") (pintype "passive"))
      (node (ref "X11") (pin "7") (pinfunction "KL_7") (pintype "passive"))
    )
    (net (code "140") (name "Net-(X11I-KL)") (class "Default")
      (node (ref "J33") (pin "1") (pinfunction "1_1") (pintype "passive"))
      (node (ref "X11") (pin "8") (pinfunction "KL_8") (pintype "passive"))
    )
    (net (code "141") (name "Net-(X11J-KL)") (class "Default")
      (node (ref "J26") (pin "2") (pinfunction "2_2") (pintype "passive"))
      (node (ref "J27") (pin "2") (pinfunction "2_2") (pintype "passive"))
      (node (ref "J28") (pin "2") (pinfunction "2_2") (pintype "passive"))
      (node (ref "J29") (pin "2") (pinfunction "2_2") (pintype "passive"))
      (node (ref "J30") (pin "2") (pinfunction "2_2") (pintype "passive"))
      (node (ref "J31") (pin "2") (pinfunction "2_2") (pintype "passive"))
      (node (ref "J32") (pin "2") (pinfunction "2_2") (pintype "passive"))
      (node (ref "J33") (pin "2") (pinfunction "2_2") (pintype "passive"))
      (node (ref "X11") (pin "9") (pinfunction "KL_9") (pintype "passive"))
    )
    (net (code "142") (name "Net-(X12A-KL)") (class "Default")
      (node (ref "X12") (pin "1") (pinfunction "KL_1") (pintype "passive"))
      (node (ref "X12") (pin "2") (pinfunction "KL_2") (pintype "passive"))
    )
    (net (code "143") (name "Net-(X12F-KL)") (class "Default")
      (node (ref "R21") (pin "1") (pinfunction "1_1") (pintype "passive"))
      (node (ref "X12") (pin "5") (pinfunction "KL_5") (pintype "passive"))
      (node (ref "X12") (pin "6") (pinfunction "KL_6") (pintype "passive"))
    )
    (net (code "144") (name "Net-(X12H-KL)") (class "Default")
      (node (ref "R23") (pin "1") (pinfunction "1_1") (pintype "passive"))
      (node (ref "X12") (pin "7") (pinfunction "KL_7") (pintype "passive"))
      (node (ref "X12") (pin "8") (pinfunction "KL_8") (pintype "passive"))
    )
    (net (code "145") (name "Net-(X15A-KL)") (class "Default")
      (node (ref "X15") (pin "1") (pinfunction "KL_1") (pintype "passive"))
      (node (ref "X15") (pin "2") (pinfunction "KL_2") (pintype "passive"))
    )
    (net (code "146") (name "Net-(X15F-KL)") (class "Default")
      (node (ref "R25") (pin "1") (pinfunction "1_1") (pintype "passive"))
      (node (ref "X15") (pin "5") (pinfunction "KL_5") (pintype "passive"))
      (node (ref "X15") (pin "6") (pinfunction "KL_6") (pintype "passive"))
    )
    (net (code "147") (name "Net-(X15H-KL)") (class "Default")
      (node (ref "R27") (pin "1") (pinfunction "1_1") (pintype "passive"))
      (node (ref "X15") (pin "7") (pinfunction "KL_7") (pintype "passive"))
      (node (ref "X15") (pin "8") (pinfunction "KL_8") (pintype "passive"))
    )
    (net (code "148") (name "Net-(X17A-KL)") (class "Default")
      (node (ref "X17") (pin "1") (pinfunction "KL_1") (pintype "passive"))
      (node (ref "X17") (pin "2") (pinfunction "KL_2") (pintype "passive"))
    )
    (net (code "149") (name "Net-(X17F-KL)") (class "Default")
      (node (ref "R29") (pin "1") (pinfunction "1_1") (pintype "passive"))
      (node (ref "X17") (pin "5") (pinfunction "KL_5") (pintype "passive"))
      (node (ref "X17") (pin "6") (pinfunction "KL_6") (pintype "passive"))
    )
    (net (code "150") (name "Net-(X17H-KL)") (class "Default")
      (node (ref "R31") (pin "1") (pinfunction "1_1") (pintype "passive"))
      (node (ref "X17") (pin "7") (pinfunction "KL_7") (pintype "passive"))
      (node (ref "X17") (pin "8") (pinfunction "KL_8") (pintype "passive"))
    )
    (net (code "151") (name "Net-(X19A-KL)") (class "Default")
      (node (ref "X19") (pin "1") (pinfunction "KL_1") (pintype "passive"))
      (node (ref "X19") (pin "2") (pinfunction "KL_2") (pintype "passive"))
    )
    (net (code "152") (name "Net-(X19F-KL)") (class "Default")
      (node (ref "R33") (pin "1") (pinfunction "1_1") (pintype "passive"))
      (node (ref "X19") (pin "5") (pinfunction "KL_5") (pintype "passive"))
      (node (ref "X19") (pin "6") (pinfunction "KL_6") (pintype "passive"))
    )
    (net (code "153") (name "Net-(X19H-KL)") (class "Default")
      (node (ref "R35") (pin "1") (pinfunction "1_1") (pintype "passive"))
      (node (ref "X19") (pin "7") (pinfunction "KL_7") (pintype "passive"))
      (node (ref "X19") (pin "8") (pinfunction "KL_8") (pintype "passive"))
    )
    (net (code "154") (name "Net-(X21A-KL)") (class "Default")
      (node (ref "X21") (pin "1") (pinfunction "KL_1") (pintype "passive"))
      (node (ref "X21") (pin "2") (pinfunction "KL_2") (pintype "passive"))
    )
    (net (code "155") (name "Net-(X21F-KL)") (class "Default")
      (node (ref "R37") (pin "1") (pinfunction "1_1") (pintype "passive"))
      (node (ref "X21") (pin "5") (pinfunction "KL_5") (pintype "passive"))
      (node (ref "X21") (pin "6") (pinfunction "KL_6") (pintype "passive"))
    )
    (net (code "156") (name "Net-(X21H-KL)") (class "Default")
      (node (ref "R39") (pin "1") (pinfunction "1_1") (pintype "passive"))
      (node (ref "X21") (pin "7") (pinfunction "KL_7") (pintype "passive"))
      (node (ref "X21") (pin "8") (pinfunction "KL_8") (pintype "passive"))
    )
    (net (code "157") (name "Net-(X23A-KL)") (class "Default")
      (node (ref "R41") (pin "1") (pinfunction "1_1") (pintype "passive"))
      (node (ref "X23") (pin "1") (pinfunction "KL_1") (pintype "passive"))
    )
    (net (code "158") (name "Net-(X23C-KL)") (class "Default")
      (node (ref "R42") (pin "1") (pinfunction "1_1") (pintype "passive"))
      (node (ref "X23") (pin "2") (pinfunction "KL_2") (pintype "passive"))
    )
    (net (code "159") (name "Net-(X23D-KL)") (class "Default")
      (node (ref "R45") (pin "1") (pinfunction "1_1") (pintype "passive"))
      (node (ref "X23") (pin "3") (pinfunction "KL_3") (pintype "passive"))
    )
    (net (code "160") (name "Net-(X23E-KL)") (class "Default")
      (node (ref "R47") (pin "1") (pinfunction "1_1") (pintype "passive"))
      (node (ref "X23") (pin "4") (pinfunction "KL_4") (pintype "passive"))
    )
    (net (code "161") (name "Net-(X23F-KL)") (class "Default")
      (node (ref "R49") (pin "1") (pinfunction "1_1") (pintype "passive"))
      (node (ref "X23") (pin "5") (pinfunction "KL_5") (pintype "passive"))
    )
    (net (code "162") (name "Net-(X23G-KL)") (class "Default")
      (node (ref "R51") (pin "1") (pinfunction "1_1") (pintype "passive"))
      (node (ref "X23") (pin "6") (pinfunction "KL_6") (pintype "passive"))
    )
    (net (code "163") (name "Net-(X23H-KL)") (class "Default")
      (node (ref "R53") (pin "1") (pinfunction "1_1") (pintype "passive"))
      (node (ref "X23") (pin "7") (pinfunction "KL_7") (pintype "passive"))
    )
    (net (code "164") (name "Net-(X25A-KL)") (class "Default")
      (node (ref "X25") (pin "1") (pinfunction "KL_1") (pintype "passive"))
      (node (ref "X25") (pin "2") (pinfunction "KL_2") (pintype "passive"))
    )
    (net (code "165") (name "Net-(X25F-KL)") (class "Default")
      (node (ref "R55") (pin "1") (pinfunction "1_1") (pintype "passive"))
      (node (ref "X25") (pin "5") (pinfunction "KL_5") (pintype "passive"))
      (node (ref "X25") (pin "6") (pinfunction "KL_6") (pintype "passive"))
    )
    (net (code "166") (name "Net-(X25H-KL)") (class "Default")
      (node (ref "R57") (pin "1") (pinfunction "1_1") (pintype "passive"))
      (node (ref "X25") (pin "7") (pinfunction "KL_7") (pintype "passive"))
      (node (ref "X25") (pin "8") (pinfunction "KL_8") (pintype "passive"))
    )
    (net (code "167") (name "VCC") (class "Default")
      (node (ref "C8") (pin "+") (pinfunction "+_+") (pintype "passive"))
      (node (ref "IC3") (pin "3") (pinfunction "VO_3") (pintype "passive"))
      (node (ref "J36") (pin "3") (pinfunction "3_3") (pintype "passive"))
      (node (ref "J37") (pin "3") (pinfunction "3_3") (pintype "passive"))
      (node (ref "OK1") (pin "4") (pinfunction "COL_4") (pintype "passive"))
      (node (ref "OK10") (pin "4") (pinfunction "COL_4") (pintype "passive"))
      (node (ref "OK11") (pin "4") (pinfunction "COL_4") (pintype "passive"))
      (node (ref "OK12") (pin "4") (pinfunction "COL_4") (pintype "passive"))
      (node (ref "OK13") (pin "4") (pinfunction "COL_4") (pintype "passive"))
      (node (ref "OK14") (pin "4") (pinfunction "COL_4") (pintype "passive"))
      (node (ref "OK15") (pin "4") (pinfunction "COL_4") (pintype "passive"))
      (node (ref "OK16") (pin "4") (pinfunction "COL_4") (pintype "passive"))
      (node (ref "OK17") (pin "4") (pinfunction "COL_4") (pintype "passive"))
      (node (ref "OK18") (pin "4") (pinfunction "COL_4") (pintype "passive"))
      (node (ref "OK19") (pin "4") (pinfunction "COL_4") (pintype "passive"))
      (node (ref "OK2") (pin "4") (pinfunction "COL_4") (pintype "passive"))
      (node (ref "OK20") (pin "4") (pinfunction "COL_4") (pintype "passive"))
      (node (ref "OK21") (pin "4") (pinfunction "COL_4") (pintype "passive"))
      (node (ref "OK3") (pin "4") (pinfunction "COL_4") (pintype "passive"))
      (node (ref "OK4") (pin "4") (pinfunction "COL_4") (pintype "passive"))
      (node (ref "OK5") (pin "4") (pinfunction "COL_4") (pintype "passive"))
      (node (ref "OK6") (pin "4") (pinfunction "COL_4") (pintype "passive"))
      (node (ref "OK7") (pin "4") (pinfunction "COL_4") (pintype "passive"))
      (node (ref "OK8") (pin "4") (pinfunction "COL_4") (pintype "passive"))
      (node (ref "OK9") (pin "4") (pinfunction "COL_4") (pintype "passive"))
      (node (ref "X13") (pin "1") (pinfunction "KL_1") (pintype "passive"))
      (node (ref "X13") (pin "2") (pinfunction "KL_2") (pintype "passive"))
      (node (ref "X16") (pin "1") (pinfunction "KL_1") (pintype "passive"))
      (node (ref "X16") (pin "2") (pinfunction "KL_2") (pintype "passive"))
      (node (ref "X18") (pin "1") (pinfunction "KL_1") (pintype "passive"))
      (node (ref "X18") (pin "2") (pinfunction "KL_2") (pintype "passive"))
      (node (ref "X20") (pin "1") (pinfunction "KL_1") (pintype "passive"))
      (node (ref "X20") (pin "2") (pinfunction "KL_2") (pintype "passive"))
      (node (ref "X22") (pin "1") (pinfunction "KL_1") (pintype "passive"))
      (node (ref "X22") (pin "2") (pinfunction "KL_2") (pintype "passive"))
      (node (ref "X26") (pin "1") (pinfunction "KL_1") (pintype "passive"))
      (node (ref "X26") (pin "2") (pinfunction "KL_2") (pintype "passive"))
    )
    (net (code "168") (name "unconnected-(J17-Pad3)") (class "Default")
      (node (ref "J17") (pin "3") (pinfunction "3_3") (pintype "passive"))
    )
    (net (code "169") (name "unconnected-(J18-Pad3)") (class "Default")
      (node (ref "J18") (pin "3") (pinfunction "3_3") (pintype "passive"))
    )
    (net (code "170") (name "unconnected-(J34-Pad3)") (class "Default")
      (node (ref "J34") (pin "3") (pinfunction "3_3") (pintype "passive"))
    )
    (net (code "171") (name "unconnected-(J35-Pad3)") (class "Default")
      (node (ref "J35") (pin "3") (pinfunction "3_3") (pintype "passive"))
    )
    (net (code "172") (name "unconnected-(X1B-KL-Pad10)") (class "Default")
      (node (ref "X1") (pin "10") (pinfunction "KL_10") (pintype "passive"))
    )
    (net (code "173") (name "unconnected-(X1I-KL-Pad8)") (class "Default")
      (node (ref "X1") (pin "8") (pinfunction "KL_8") (pintype "passive"))
    )
    (net (code "174") (name "unconnected-(X3B-KL-Pad10)") (class "Default")
      (node (ref "X3") (pin "10") (pinfunction "KL_10") (pintype "passive"))
    )
    (net (code "175") (name "unconnected-(X3I-KL-Pad8)") (class "Default")
      (node (ref "X3") (pin "8") (pinfunction "KL_8") (pintype "passive"))
    )
    (net (code "176") (name "unconnected-(X10B-KL-Pad10)") (class "Default")
      (node (ref "X10") (pin "10") (pinfunction "KL_10") (pintype "passive"))
    )
    (net (code "177") (name "unconnected-(X11B-KL-Pad10)") (class "Default")
      (node (ref "X11") (pin "10") (pinfunction "KL_10") (pintype "passive"))
    )
    (net (code "178") (name "unconnected-(X12B-KL-Pad10)") (class "Default")
      (node (ref "X12") (pin "10") (pinfunction "KL_10") (pintype "passive"))
    )
    (net (code "179") (name "unconnected-(X12J-KL-Pad9)") (class "Default")
      (node (ref "X12") (pin "9") (pinfunction "KL_9") (pintype "passive"))
    )
    (net (code "180") (name "unconnected-(X13B-KL-Pad10)") (class "Default")
      (node (ref "X13") (pin "10") (pinfunction "KL_10") (pintype "passive"))
    )
    (net (code "181") (name "unconnected-(X13J-KL-Pad9)") (class "Default")
      (node (ref "X13") (pin "9") (pinfunction "KL_9") (pintype "passive"))
    )
    (net (code "182") (name "unconnected-(X15B-KL-Pad10)") (class "Default")
      (node (ref "X15") (pin "10") (pinfunction "KL_10") (pintype "passive"))
    )
    (net (code "183") (name "unconnected-(X15J-KL-Pad9)") (class "Default")
      (node (ref "X15") (pin "9") (pinfunction "KL_9") (pintype "passive"))
    )
    (net (code "184") (name "unconnected-(X16B-KL-Pad10)") (class "Default")
      (node (ref "X16") (pin "10") (pinfunction "KL_10") (pintype "passive"))
    )
    (net (code "185") (name "unconnected-(X16J-KL-Pad9)") (class "Default")
      (node (ref "X16") (pin "9") (pinfunction "KL_9") (pintype "passive"))
    )
    (net (code "186") (name "unconnected-(X17B-KL-Pad10)") (class "Default")
      (node (ref "X17") (pin "10") (pinfunction "KL_10") (pintype "passive"))
    )
    (net (code "187") (name "unconnected-(X17J-KL-Pad9)") (class "Default")
      (node (ref "X17") (pin "9") (pinfunction "KL_9") (pintype "passive"))
    )
    (net (code "188") (name "unconnected-(X18B-KL-Pad10)") (class "Default")
      (node (ref "X18") (pin "10") (pinfunction "KL_10") (pintype "passive"))
    )
    (net (code "189") (name "unconnected-(X18J-KL-Pad9)") (class "Default")
      (node (ref "X18") (pin "9") (pinfunction "KL_9") (pintype "passive"))
    )
    (net (code "190") (name "unconnected-(X19B-KL-Pad10)") (class "Default")
      (node (ref "X19") (pin "10") (pinfunction "KL_10") (pintype "passive"))
    )
    (net (code "191") (name "unconnected-(X19J-KL-Pad9)") (class "Default")
      (node (ref "X19") (pin "9") (pinfunction "KL_9") (pintype "passive"))
    )
    (net (code "192") (name "unconnected-(X20B-KL-Pad10)") (class "Default")
      (node (ref "X20") (pin "10") (pinfunction "KL_10") (pintype "passive"))
    )
    (net (code "193") (name "unconnected-(X20J-KL-Pad9)") (class "Default")
      (node (ref "X20") (pin "9") (pinfunction "KL_9") (pintype "passive"))
    )
    (net (code "194") (name "unconnected-(X21B-KL-Pad10)") (class "Default")
      (node (ref "X21") (pin "10") (pinfunction "KL_10") (pintype "passive"))
    )
    (net (code "195") (name "unconnected-(X21J-KL-Pad9)") (class "Default")
      (node (ref "X21") (pin "9") (pinfunction "KL_9") (pintype "passive"))
    )
    (net (code "196") (name "unconnected-(X22B-KL-Pad10)") (class "Default")
      (node (ref "X22") (pin "10") (pinfunction "KL_10") (pintype "passive"))
    )
    (net (code "197") (name "unconnected-(X22J-KL-Pad9)") (class "Default")
      (node (ref "X22") (pin "9") (pinfunction "KL_9") (pintype "passive"))
    )
    (net (code "198") (name "unconnected-(X23B-KL-Pad10)") (class "Default")
      (node (ref "X23") (pin "10") (pinfunction "KL_10") (pintype "passive"))
    )
    (net (code "199") (name "unconnected-(X23I-KL-Pad8)") (class "Default")
      (node (ref "X23") (pin "8") (pinfunction "KL_8") (pintype "passive"))
    )
    (net (code "200") (name "unconnected-(X24B-KL-Pad10)") (class "Default")
      (node (ref "X24") (pin "10") (pinfunction "KL_10") (pintype "passive"))
    )
    (net (code "201") (name "unconnected-(X24I-KL-Pad8)") (class "Default")
      (node (ref "X24") (pin "8") (pinfunction "KL_8") (pintype "passive"))
    )
    (net (code "202") (name "unconnected-(X24J-KL-Pad9)") (class "Default")
      (node (ref "X24") (pin "9") (pinfunction "KL_9") (pintype "passive"))
    )
    (net (code "203") (name "unconnected-(X25B-KL-Pad10)") (class "Default")
      (node (ref "X25") (pin "10") (pinfunction "KL_10") (pintype "passive"))
    )
    (net (code "204") (name "unconnected-(X25J-KL-Pad9)") (class "Default")
      (node (ref "X25") (pin "9") (pinfunction "KL_9") (pintype "passive"))
    )
    (net (code "205") (name "unconnected-(X26B-KL-Pad10)") (class "Default")
      (node (ref "X26") (pin "10") (pinfunction "KL_10") (pintype "passive"))
    )
    (net (code "206") (name "unconnected-(X26J-KL-Pad9)") (class "Default")
      (node (ref "X26") (pin "9") (pinfunction "KL_9") (pintype "passive"))
    )
  )
)
